# BackBoard.net
KiCad netlist of a schematic drawn in Altium Designer
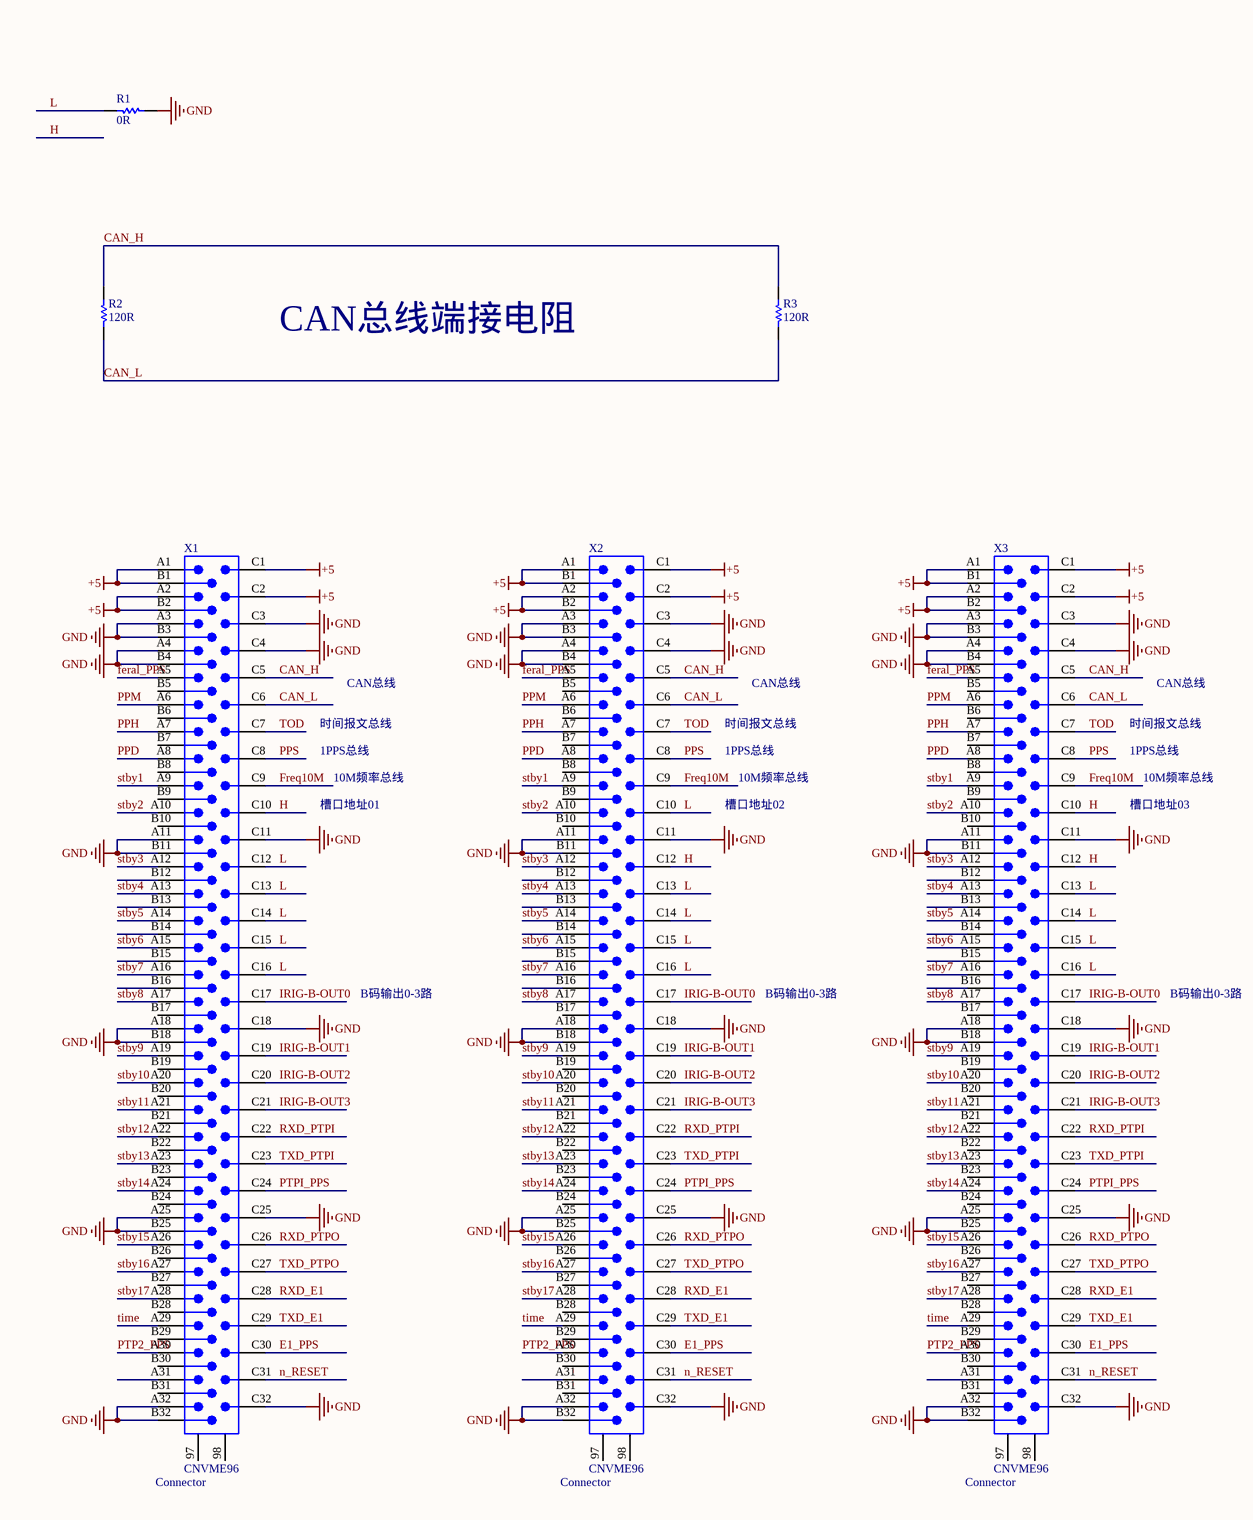
[diagram p0: BackBoard.SchDoc, top left]
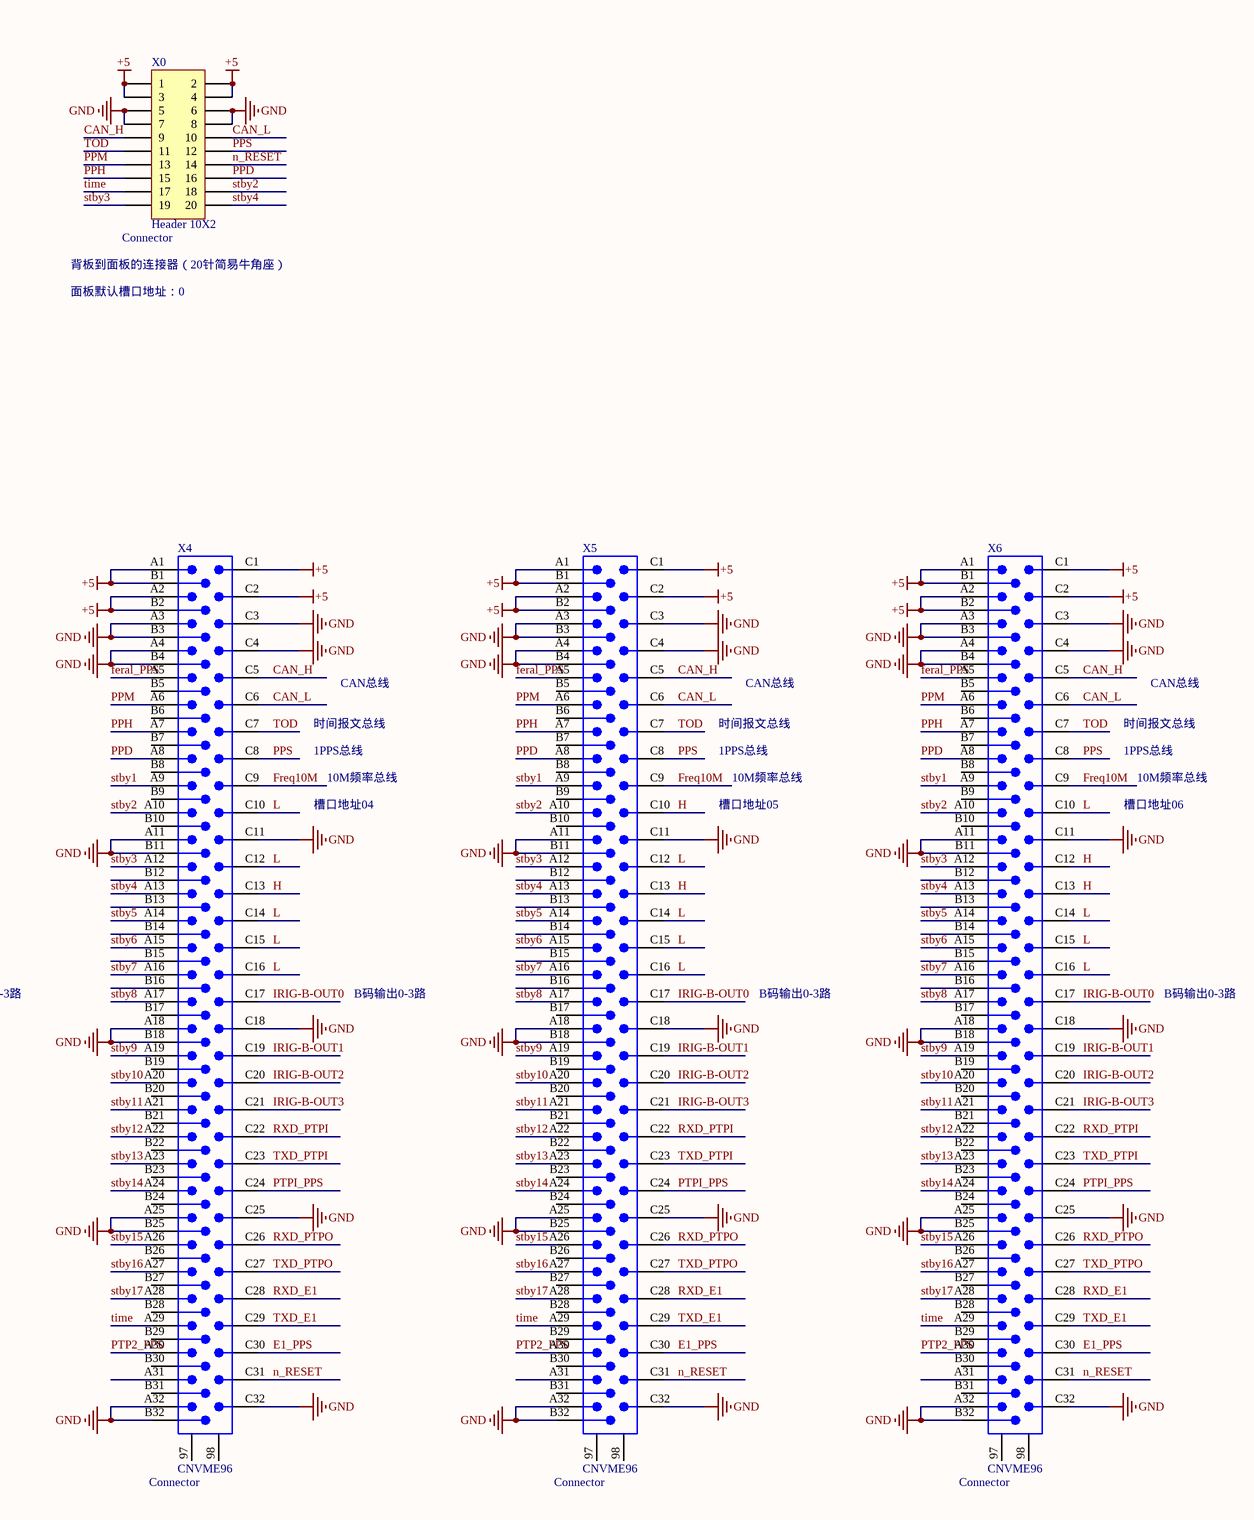
[diagram p1: BackBoard.SchDoc, top right]
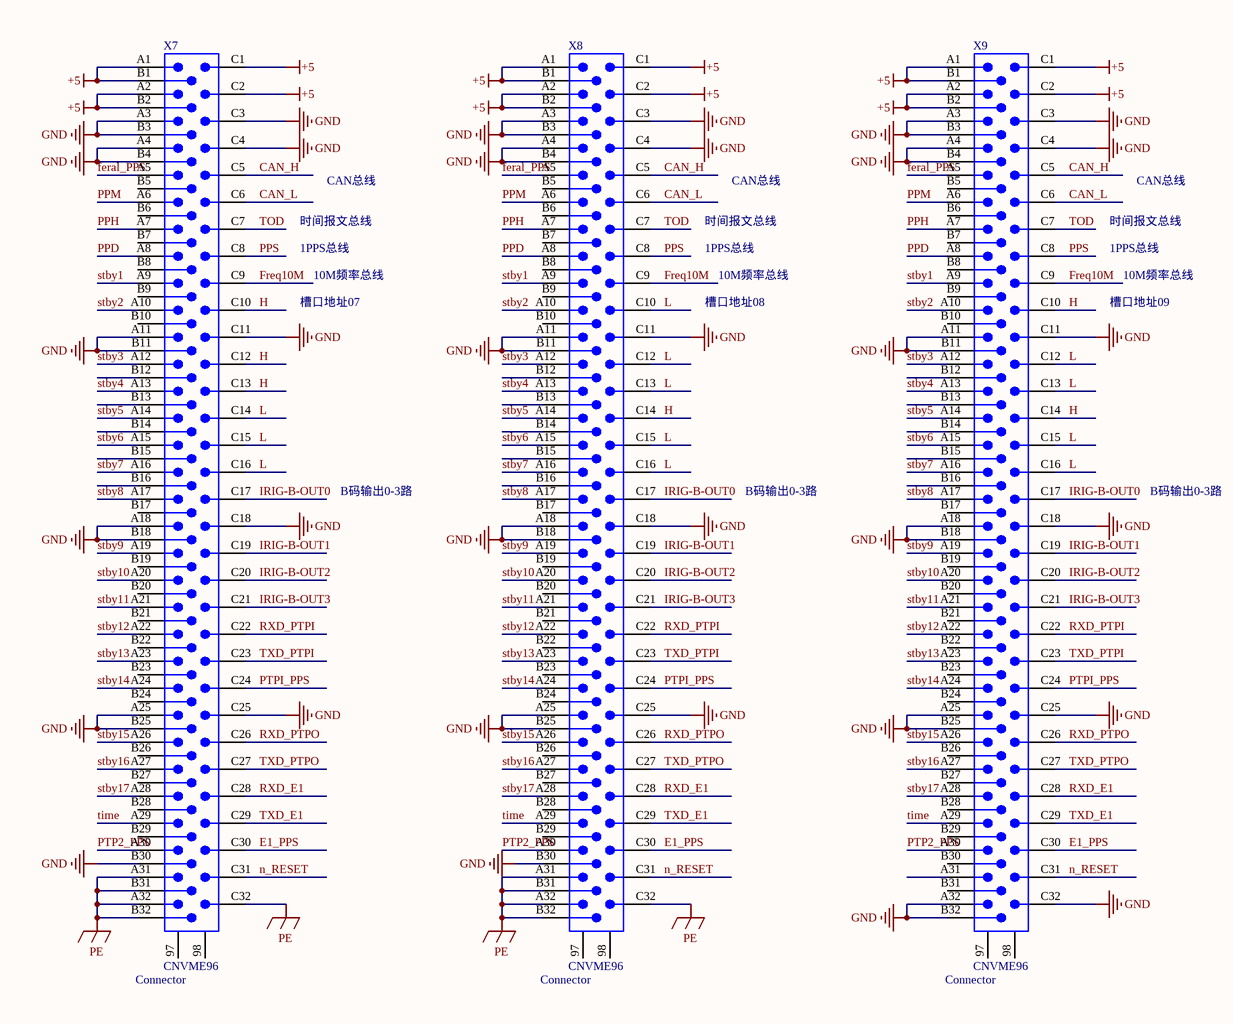
[diagram p2: BackBoard.SchDoc, bottom left]
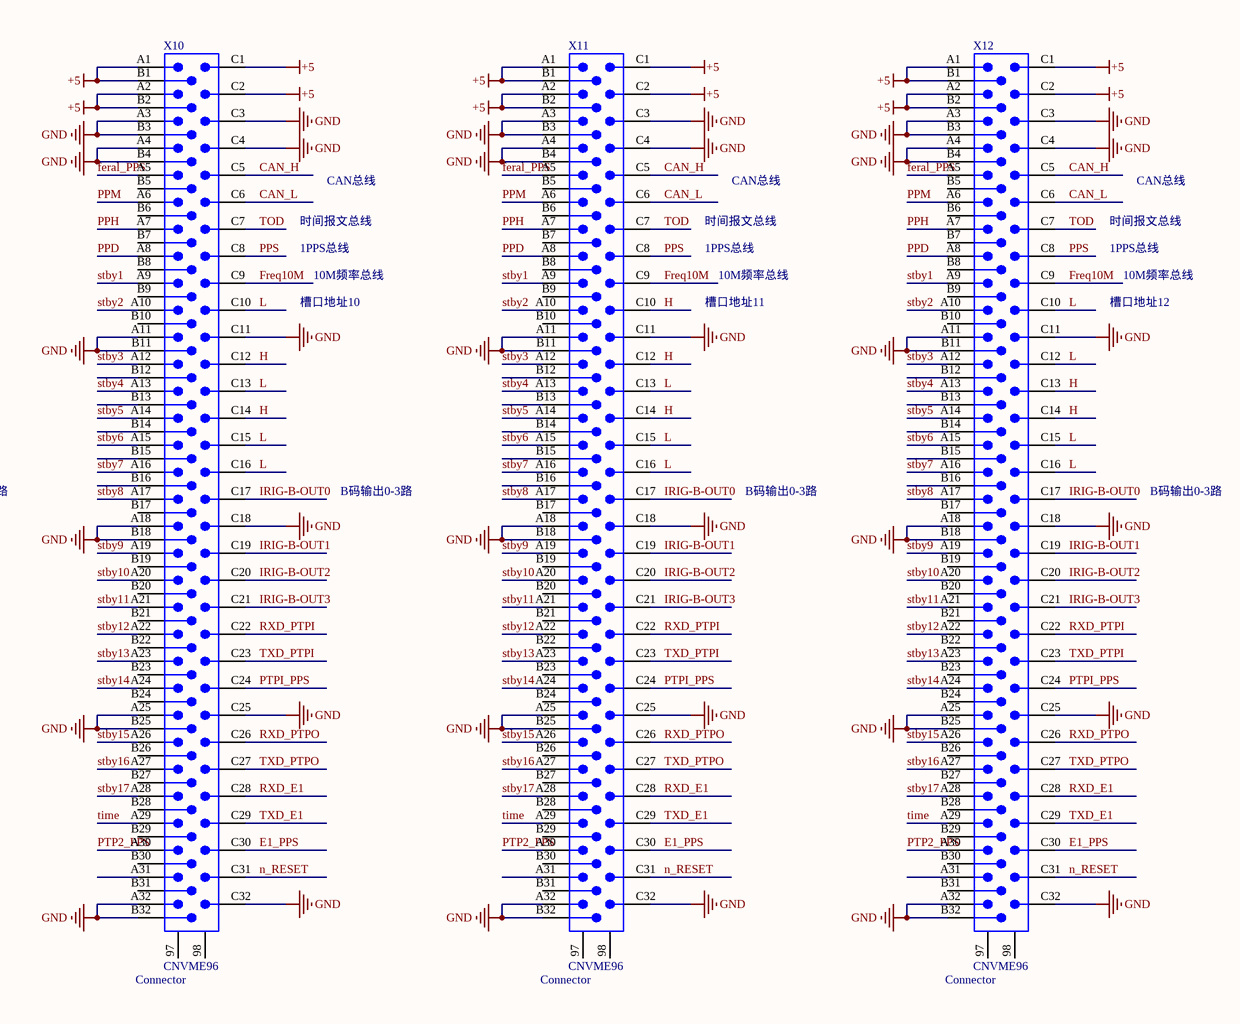
[diagram p3: BackBoard.SchDoc, bottom right]

(export (version "E")
  (design (tool "Eeschema 10.0.6"))
  (components
    (comp (ref "R1")
      (value "0R")
      (footprint "0603_XF")
      (description "Resistor")
      (fields (field (name "Comment") "Res1") (field (name "PUBLISHER") "Altium Limited"))
      (libsource (lib "Miscellaneous Devices") (part "Res1"))
    )
    (comp (ref "R2")
      (value "120R")
      (footprint "0603_XF")
      (description "Resistor")
      (fields (field (name "Comment") "Res1") (field (name "PUBLISHER") "Altium Limited"))
      (libsource (lib "Miscellaneous Devices") (part "Res1"))
    )
    (comp (ref "R3")
      (value "120R")
      (footprint "0603_XF")
      (description "Resistor")
      (fields (field (name "Comment") "Res1") (field (name "PUBLISHER") "Altium Limited"))
      (libsource (lib "Miscellaneous Devices") (part "Res1"))
    )
    (comp (ref "X0")
      (value "Header 10X2")
      (footprint "HDR2X10")
      (description "Header, 10-Pin, Dual row")
      (fields (field (name "SYSTEM") "Connector") (field (name "PUBLISHER") "Altium Limited"))
      (libsource (lib "Miscellaneous Connectors") (part "Header 10X2"))
    )
    (comp (ref "X1")
      (value "CNVME96")
      (footprint "CONNECT_96_Female")
      (description "96-Pin Connector (3x32 2.54mm grid)")
      (fields (field (name "SYSTEM") "Connector"))
      (libsource (lib "BTS4000") (part "CNVME96"))
    )
    (comp (ref "X2")
      (value "CNVME96")
      (footprint "CONNECT_96_Female")
      (description "96-Pin Connector (3x32 2.54mm grid)")
      (fields (field (name "SYSTEM") "Connector"))
      (libsource (lib "BTS4000") (part "CNVME96"))
    )
    (comp (ref "X3")
      (value "CNVME96")
      (footprint "CONNECT_96_Female")
      (description "96-Pin Connector (3x32 2.54mm grid)")
      (fields (field (name "SYSTEM") "Connector"))
      (libsource (lib "BTS4000") (part "CNVME96"))
    )
    (comp (ref "X4")
      (value "CNVME96")
      (footprint "CONNECT_96_Female")
      (description "96-Pin Connector (3x32 2.54mm grid)")
      (fields (field (name "SYSTEM") "Connector"))
      (libsource (lib "BTS4000") (part "CNVME96"))
    )
    (comp (ref "X5")
      (value "CNVME96")
      (footprint "CONNECT_96_Female")
      (description "96-Pin Connector (3x32 2.54mm grid)")
      (fields (field (name "SYSTEM") "Connector"))
      (libsource (lib "BTS4000") (part "CNVME96"))
    )
    (comp (ref "X6")
      (value "CNVME96")
      (footprint "CONNECT_96_Female")
      (description "96-Pin Connector (3x32 2.54mm grid)")
      (fields (field (name "SYSTEM") "Connector"))
      (libsource (lib "BTS4000") (part "CNVME96"))
    )
    (comp (ref "X7")
      (value "CNVME96")
      (footprint "CONNECT_96_Female")
      (description "96-Pin Connector (3x32 2.54mm grid)")
      (fields (field (name "SYSTEM") "Connector"))
      (libsource (lib "BTS4000") (part "CNVME96"))
    )
    (comp (ref "X8")
      (value "CNVME96")
      (footprint "CONNECT_96_Female")
      (description "96-Pin Connector (3x32 2.54mm grid)")
      (fields (field (name "SYSTEM") "Connector"))
      (libsource (lib "BTS4000") (part "CNVME96"))
    )
    (comp (ref "X9")
      (value "CNVME96")
      (footprint "CONNECT_96_Female")
      (description "96-Pin Connector (3x32 2.54mm grid)")
      (fields (field (name "SYSTEM") "Connector"))
      (libsource (lib "BTS4000") (part "CNVME96"))
    )
    (comp (ref "X10")
      (value "CNVME96")
      (footprint "CONNECT_96_Female")
      (description "96-Pin Connector (3x32 2.54mm grid)")
      (fields (field (name "SYSTEM") "Connector"))
      (libsource (lib "BTS4000") (part "CNVME96"))
    )
    (comp (ref "X11")
      (value "CNVME96")
      (footprint "CONNECT_96_Female")
      (description "96-Pin Connector (3x32 2.54mm grid)")
      (fields (field (name "SYSTEM") "Connector"))
      (libsource (lib "BTS4000") (part "CNVME96"))
    )
    (comp (ref "X12")
      (value "CNVME96")
      (footprint "CONNECT_96_Female")
      (description "96-Pin Connector (3x32 2.54mm grid)")
      (fields (field (name "SYSTEM") "Connector"))
      (libsource (lib "BTS4000") (part "CNVME96"))
    )
  )
  (nets
    (net (code "1") (name "+5") (class "Default")
      (node (ref "X0") (pin "1") (pinfunction "1_1") (pintype "passive"))
      (node (ref "X0") (pin "2") (pinfunction "2_2") (pintype "passive"))
      (node (ref "X0") (pin "3") (pinfunction "3_3") (pintype "passive"))
      (node (ref "X0") (pin "4") (pinfunction "4_4") (pintype "passive"))
      (node (ref "X1") (pin "A1") (pinfunction "A1_A1") (pintype "passive"))
      (node (ref "X1") (pin "A2") (pinfunction "A2_A2") (pintype "passive"))
      (node (ref "X1") (pin "B1") (pinfunction "B1_B1") (pintype "passive"))
      (node (ref "X1") (pin "B2") (pinfunction "B2_B2") (pintype "passive"))
      (node (ref "X1") (pin "C1") (pinfunction "C1_C1") (pintype "passive"))
      (node (ref "X1") (pin "C2") (pinfunction "C2_C2") (pintype "passive"))
      (node (ref "X10") (pin "A1") (pinfunction "A1_A1") (pintype "passive"))
      (node (ref "X10") (pin "A2") (pinfunction "A2_A2") (pintype "passive"))
      (node (ref "X10") (pin "B1") (pinfunction "B1_B1") (pintype "passive"))
      (node (ref "X10") (pin "B2") (pinfunction "B2_B2") (pintype "passive"))
      (node (ref "X10") (pin "C1") (pinfunction "C1_C1") (pintype "passive"))
      (node (ref "X10") (pin "C2") (pinfunction "C2_C2") (pintype "passive"))
      (node (ref "X11") (pin "A1") (pinfunction "A1_A1") (pintype "passive"))
      (node (ref "X11") (pin "A2") (pinfunction "A2_A2") (pintype "passive"))
      (node (ref "X11") (pin "B1") (pinfunction "B1_B1") (pintype "passive"))
      (node (ref "X11") (pin "B2") (pinfunction "B2_B2") (pintype "passive"))
      (node (ref "X11") (pin "C1") (pinfunction "C1_C1") (pintype "passive"))
      (node (ref "X11") (pin "C2") (pinfunction "C2_C2") (pintype "passive"))
      (node (ref "X12") (pin "A1") (pinfunction "A1_A1") (pintype "passive"))
      (node (ref "X12") (pin "A2") (pinfunction "A2_A2") (pintype "passive"))
      (node (ref "X12") (pin "B1") (pinfunction "B1_B1") (pintype "passive"))
      (node (ref "X12") (pin "B2") (pinfunction "B2_B2") (pintype "passive"))
      (node (ref "X12") (pin "C1") (pinfunction "C1_C1") (pintype "passive"))
      (node (ref "X12") (pin "C2") (pinfunction "C2_C2") (pintype "passive"))
      (node (ref "X2") (pin "A1") (pinfunction "A1_A1") (pintype "passive"))
      (node (ref "X2") (pin "A2") (pinfunction "A2_A2") (pintype "passive"))
      (node (ref "X2") (pin "B1") (pinfunction "B1_B1") (pintype "passive"))
      (node (ref "X2") (pin "B2") (pinfunction "B2_B2") (pintype "passive"))
      (node (ref "X2") (pin "C1") (pinfunction "C1_C1") (pintype "passive"))
      (node (ref "X2") (pin "C2") (pinfunction "C2_C2") (pintype "passive"))
      (node (ref "X3") (pin "A1") (pinfunction "A1_A1") (pintype "passive"))
      (node (ref "X3") (pin "A2") (pinfunction "A2_A2") (pintype "passive"))
      (node (ref "X3") (pin "B1") (pinfunction "B1_B1") (pintype "passive"))
      (node (ref "X3") (pin "B2") (pinfunction "B2_B2") (pintype "passive"))
      (node (ref "X3") (pin "C1") (pinfunction "C1_C1") (pintype "passive"))
      (node (ref "X3") (pin "C2") (pinfunction "C2_C2") (pintype "passive"))
      (node (ref "X4") (pin "A1") (pinfunction "A1_A1") (pintype "passive"))
      (node (ref "X4") (pin "A2") (pinfunction "A2_A2") (pintype "passive"))
      (node (ref "X4") (pin "B1") (pinfunction "B1_B1") (pintype "passive"))
      (node (ref "X4") (pin "B2") (pinfunction "B2_B2") (pintype "passive"))
      (node (ref "X4") (pin "C1") (pinfunction "C1_C1") (pintype "passive"))
      (node (ref "X4") (pin "C2") (pinfunction "C2_C2") (pintype "passive"))
      (node (ref "X5") (pin "A1") (pinfunction "A1_A1") (pintype "passive"))
      (node (ref "X5") (pin "A2") (pinfunction "A2_A2") (pintype "passive"))
      (node (ref "X5") (pin "B1") (pinfunction "B1_B1") (pintype "passive"))
      (node (ref "X5") (pin "B2") (pinfunction "B2_B2") (pintype "passive"))
      (node (ref "X5") (pin "C1") (pinfunction "C1_C1") (pintype "passive"))
      (node (ref "X5") (pin "C2") (pinfunction "C2_C2") (pintype "passive"))
      (node (ref "X6") (pin "A1") (pinfunction "A1_A1") (pintype "passive"))
      (node (ref "X6") (pin "A2") (pinfunction "A2_A2") (pintype "passive"))
      (node (ref "X6") (pin "B1") (pinfunction "B1_B1") (pintype "passive"))
      (node (ref "X6") (pin "B2") (pinfunction "B2_B2") (pintype "passive"))
      (node (ref "X6") (pin "C1") (pinfunction "C1_C1") (pintype "passive"))
      (node (ref "X6") (pin "C2") (pinfunction "C2_C2") (pintype "passive"))
      (node (ref "X7") (pin "A1") (pinfunction "A1_A1") (pintype "passive"))
      (node (ref "X7") (pin "A2") (pinfunction "A2_A2") (pintype "passive"))
      (node (ref "X7") (pin "B1") (pinfunction "B1_B1") (pintype "passive"))
      (node (ref "X7") (pin "B2") (pinfunction "B2_B2") (pintype "passive"))
      (node (ref "X7") (pin "C1") (pinfunction "C1_C1") (pintype "passive"))
      (node (ref "X7") (pin "C2") (pinfunction "C2_C2") (pintype "passive"))
      (node (ref "X8") (pin "A1") (pinfunction "A1_A1") (pintype "passive"))
      (node (ref "X8") (pin "A2") (pinfunction "A2_A2") (pintype "passive"))
      (node (ref "X8") (pin "B1") (pinfunction "B1_B1") (pintype "passive"))
      (node (ref "X8") (pin "B2") (pinfunction "B2_B2") (pintype "passive"))
      (node (ref "X8") (pin "C1") (pinfunction "C1_C1") (pintype "passive"))
      (node (ref "X8") (pin "C2") (pinfunction "C2_C2") (pintype "passive"))
      (node (ref "X9") (pin "A1") (pinfunction "A1_A1") (pintype "passive"))
      (node (ref "X9") (pin "A2") (pinfunction "A2_A2") (pintype "passive"))
      (node (ref "X9") (pin "B1") (pinfunction "B1_B1") (pintype "passive"))
      (node (ref "X9") (pin "B2") (pinfunction "B2_B2") (pintype "passive"))
      (node (ref "X9") (pin "C1") (pinfunction "C1_C1") (pintype "passive"))
      (node (ref "X9") (pin "C2") (pinfunction "C2_C2") (pintype "passive"))
    )
    (net (code "2") (name "/CAN_H") (class "Default")
      (node (ref "R2") (pin "1") (pinfunction "1_1") (pintype "passive"))
      (node (ref "R3") (pin "2") (pinfunction "2_2") (pintype "passive"))
      (node (ref "X0") (pin "9") (pinfunction "9_9") (pintype "passive"))
      (node (ref "X1") (pin "C5") (pinfunction "C5_C5") (pintype "passive"))
      (node (ref "X10") (pin "C5") (pinfunction "C5_C5") (pintype "passive"))
      (node (ref "X11") (pin "C5") (pinfunction "C5_C5") (pintype "passive"))
      (node (ref "X12") (pin "C5") (pinfunction "C5_C5") (pintype "passive"))
      (node (ref "X2") (pin "C5") (pinfunction "C5_C5") (pintype "passive"))
      (node (ref "X3") (pin "C5") (pinfunction "C5_C5") (pintype "passive"))
      (node (ref "X4") (pin "C5") (pinfunction "C5_C5") (pintype "passive"))
      (node (ref "X5") (pin "C5") (pinfunction "C5_C5") (pintype "passive"))
      (node (ref "X6") (pin "C5") (pinfunction "C5_C5") (pintype "passive"))
      (node (ref "X7") (pin "C5") (pinfunction "C5_C5") (pintype "passive"))
      (node (ref "X8") (pin "C5") (pinfunction "C5_C5") (pintype "passive"))
      (node (ref "X9") (pin "C5") (pinfunction "C5_C5") (pintype "passive"))
    )
    (net (code "3") (name "/CAN_L") (class "Default")
      (node (ref "R2") (pin "2") (pinfunction "2_2") (pintype "passive"))
      (node (ref "R3") (pin "1") (pinfunction "1_1") (pintype "passive"))
      (node (ref "X0") (pin "10") (pinfunction "10_10") (pintype "passive"))
      (node (ref "X1") (pin "C6") (pinfunction "C6_C6") (pintype "passive"))
      (node (ref "X10") (pin "C6") (pinfunction "C6_C6") (pintype "passive"))
      (node (ref "X11") (pin "C6") (pinfunction "C6_C6") (pintype "passive"))
      (node (ref "X12") (pin "C6") (pinfunction "C6_C6") (pintype "passive"))
      (node (ref "X2") (pin "C6") (pinfunction "C6_C6") (pintype "passive"))
      (node (ref "X3") (pin "C6") (pinfunction "C6_C6") (pintype "passive"))
      (node (ref "X4") (pin "C6") (pinfunction "C6_C6") (pintype "passive"))
      (node (ref "X5") (pin "C6") (pinfunction "C6_C6") (pintype "passive"))
      (node (ref "X6") (pin "C6") (pinfunction "C6_C6") (pintype "passive"))
      (node (ref "X7") (pin "C6") (pinfunction "C6_C6") (pintype "passive"))
      (node (ref "X8") (pin "C6") (pinfunction "C6_C6") (pintype "passive"))
      (node (ref "X9") (pin "C6") (pinfunction "C6_C6") (pintype "passive"))
    )
    (net (code "4") (name "/E1_PPS") (class "Default")
      (node (ref "X1") (pin "C30") (pinfunction "C30_C30") (pintype "passive"))
      (node (ref "X10") (pin "C30") (pinfunction "C30_C30") (pintype "passive"))
      (node (ref "X11") (pin "C30") (pinfunction "C30_C30") (pintype "passive"))
      (node (ref "X12") (pin "C30") (pinfunction "C30_C30") (pintype "passive"))
      (node (ref "X2") (pin "C30") (pinfunction "C30_C30") (pintype "passive"))
      (node (ref "X3") (pin "C30") (pinfunction "C30_C30") (pintype "passive"))
      (node (ref "X4") (pin "C30") (pinfunction "C30_C30") (pintype "passive"))
      (node (ref "X5") (pin "C30") (pinfunction "C30_C30") (pintype "passive"))
      (node (ref "X6") (pin "C30") (pinfunction "C30_C30") (pintype "passive"))
      (node (ref "X7") (pin "C30") (pinfunction "C30_C30") (pintype "passive"))
      (node (ref "X8") (pin "C30") (pinfunction "C30_C30") (pintype "passive"))
      (node (ref "X9") (pin "C30") (pinfunction "C30_C30") (pintype "passive"))
    )
    (net (code "5") (name "/Freq10M") (class "Default")
      (node (ref "X1") (pin "C9") (pinfunction "C9_C9") (pintype "passive"))
      (node (ref "X10") (pin "C9") (pinfunction "C9_C9") (pintype "passive"))
      (node (ref "X11") (pin "C9") (pinfunction "C9_C9") (pintype "passive"))
      (node (ref "X12") (pin "C9") (pinfunction "C9_C9") (pintype "passive"))
      (node (ref "X2") (pin "C9") (pinfunction "C9_C9") (pintype "passive"))
      (node (ref "X3") (pin "C9") (pinfunction "C9_C9") (pintype "passive"))
      (node (ref "X4") (pin "C9") (pinfunction "C9_C9") (pintype "passive"))
      (node (ref "X5") (pin "C9") (pinfunction "C9_C9") (pintype "passive"))
      (node (ref "X6") (pin "C9") (pinfunction "C9_C9") (pintype "passive"))
      (node (ref "X7") (pin "C9") (pinfunction "C9_C9") (pintype "passive"))
      (node (ref "X8") (pin "C9") (pinfunction "C9_C9") (pintype "passive"))
      (node (ref "X9") (pin "C9") (pinfunction "C9_C9") (pintype "passive"))
    )
    (net (code "6") (name "/H") (class "Default")
      (node (ref "X1") (pin "C10") (pinfunction "C10_C10") (pintype "passive"))
      (node (ref "X10") (pin "C12") (pinfunction "C12_C12") (pintype "passive"))
      (node (ref "X10") (pin "C14") (pinfunction "C14_C14") (pintype "passive"))
      (node (ref "X11") (pin "C10") (pinfunction "C10_C10") (pintype "passive"))
      (node (ref "X11") (pin "C12") (pinfunction "C12_C12") (pintype "passive"))
      (node (ref "X11") (pin "C14") (pinfunction "C14_C14") (pintype "passive"))
      (node (ref "X12") (pin "C13") (pinfunction "C13_C13") (pintype "passive"))
      (node (ref "X12") (pin "C14") (pinfunction "C14_C14") (pintype "passive"))
      (node (ref "X2") (pin "C12") (pinfunction "C12_C12") (pintype "passive"))
      (node (ref "X3") (pin "C10") (pinfunction "C10_C10") (pintype "passive"))
      (node (ref "X3") (pin "C12") (pinfunction "C12_C12") (pintype "passive"))
      (node (ref "X4") (pin "C13") (pinfunction "C13_C13") (pintype "passive"))
      (node (ref "X5") (pin "C10") (pinfunction "C10_C10") (pintype "passive"))
      (node (ref "X5") (pin "C13") (pinfunction "C13_C13") (pintype "passive"))
      (node (ref "X6") (pin "C12") (pinfunction "C12_C12") (pintype "passive"))
      (node (ref "X6") (pin "C13") (pinfunction "C13_C13") (pintype "passive"))
      (node (ref "X7") (pin "C10") (pinfunction "C10_C10") (pintype "passive"))
      (node (ref "X7") (pin "C12") (pinfunction "C12_C12") (pintype "passive"))
      (node (ref "X7") (pin "C13") (pinfunction "C13_C13") (pintype "passive"))
      (node (ref "X8") (pin "C14") (pinfunction "C14_C14") (pintype "passive"))
      (node (ref "X9") (pin "C10") (pinfunction "C10_C10") (pintype "passive"))
      (node (ref "X9") (pin "C14") (pinfunction "C14_C14") (pintype "passive"))
    )
    (net (code "7") (name "/IRIG-B-OUT0") (class "Default")
      (node (ref "X1") (pin "C17") (pinfunction "C17_C17") (pintype "passive"))
      (node (ref "X10") (pin "C17") (pinfunction "C17_C17") (pintype "passive"))
      (node (ref "X11") (pin "C17") (pinfunction "C17_C17") (pintype "passive"))
      (node (ref "X12") (pin "C17") (pinfunction "C17_C17") (pintype "passive"))
      (node (ref "X2") (pin "C17") (pinfunction "C17_C17") (pintype "passive"))
      (node (ref "X3") (pin "C17") (pinfunction "C17_C17") (pintype "passive"))
      (node (ref "X4") (pin "C17") (pinfunction "C17_C17") (pintype "passive"))
      (node (ref "X5") (pin "C17") (pinfunction "C17_C17") (pintype "passive"))
      (node (ref "X6") (pin "C17") (pinfunction "C17_C17") (pintype "passive"))
      (node (ref "X7") (pin "C17") (pinfunction "C17_C17") (pintype "passive"))
      (node (ref "X8") (pin "C17") (pinfunction "C17_C17") (pintype "passive"))
      (node (ref "X9") (pin "C17") (pinfunction "C17_C17") (pintype "passive"))
    )
    (net (code "8") (name "/IRIG-B-OUT1") (class "Default")
      (node (ref "X1") (pin "C19") (pinfunction "C19_C19") (pintype "passive"))
      (node (ref "X10") (pin "C19") (pinfunction "C19_C19") (pintype "passive"))
      (node (ref "X11") (pin "C19") (pinfunction "C19_C19") (pintype "passive"))
      (node (ref "X12") (pin "C19") (pinfunction "C19_C19") (pintype "passive"))
      (node (ref "X2") (pin "C19") (pinfunction "C19_C19") (pintype "passive"))
      (node (ref "X3") (pin "C19") (pinfunction "C19_C19") (pintype "passive"))
      (node (ref "X4") (pin "C19") (pinfunction "C19_C19") (pintype "passive"))
      (node (ref "X5") (pin "C19") (pinfunction "C19_C19") (pintype "passive"))
      (node (ref "X6") (pin "C19") (pinfunction "C19_C19") (pintype "passive"))
      (node (ref "X7") (pin "C19") (pinfunction "C19_C19") (pintype "passive"))
      (node (ref "X8") (pin "C19") (pinfunction "C19_C19") (pintype "passive"))
      (node (ref "X9") (pin "C19") (pinfunction "C19_C19") (pintype "passive"))
    )
    (net (code "9") (name "/IRIG-B-OUT2") (class "Default")
      (node (ref "X1") (pin "C20") (pinfunction "C20_C20") (pintype "passive"))
      (node (ref "X10") (pin "C20") (pinfunction "C20_C20") (pintype "passive"))
      (node (ref "X11") (pin "C20") (pinfunction "C20_C20") (pintype "passive"))
      (node (ref "X12") (pin "C20") (pinfunction "C20_C20") (pintype "passive"))
      (node (ref "X2") (pin "C20") (pinfunction "C20_C20") (pintype "passive"))
      (node (ref "X3") (pin "C20") (pinfunction "C20_C20") (pintype "passive"))
      (node (ref "X4") (pin "C20") (pinfunction "C20_C20") (pintype "passive"))
      (node (ref "X5") (pin "C20") (pinfunction "C20_C20") (pintype "passive"))
      (node (ref "X6") (pin "C20") (pinfunction "C20_C20") (pintype "passive"))
      (node (ref "X7") (pin "C20") (pinfunction "C20_C20") (pintype "passive"))
      (node (ref "X8") (pin "C20") (pinfunction "C20_C20") (pintype "passive"))
      (node (ref "X9") (pin "C20") (pinfunction "C20_C20") (pintype "passive"))
    )
    (net (code "10") (name "/IRIG-B-OUT3") (class "Default")
      (node (ref "X1") (pin "C21") (pinfunction "C21_C21") (pintype "passive"))
      (node (ref "X10") (pin "C21") (pinfunction "C21_C21") (pintype "passive"))
      (node (ref "X11") (pin "C21") (pinfunction "C21_C21") (pintype "passive"))
      (node (ref "X12") (pin "C21") (pinfunction "C21_C21") (pintype "passive"))
      (node (ref "X2") (pin "C21") (pinfunction "C21_C21") (pintype "passive"))
      (node (ref "X3") (pin "C21") (pinfunction "C21_C21") (pintype "passive"))
      (node (ref "X4") (pin "C21") (pinfunction "C21_C21") (pintype "passive"))
      (node (ref "X5") (pin "C21") (pinfunction "C21_C21") (pintype "passive"))
      (node (ref "X6") (pin "C21") (pinfunction "C21_C21") (pintype "passive"))
      (node (ref "X7") (pin "C21") (pinfunction "C21_C21") (pintype "passive"))
      (node (ref "X8") (pin "C21") (pinfunction "C21_C21") (pintype "passive"))
      (node (ref "X9") (pin "C21") (pinfunction "C21_C21") (pintype "passive"))
    )
    (net (code "11") (name "/L") (class "Default")
      (node (ref "R1") (pin "1") (pinfunction "1_1") (pintype "passive"))
      (node (ref "X1") (pin "C12") (pinfunction "C12_C12") (pintype "passive"))
      (node (ref "X1") (pin "C13") (pinfunction "C13_C13") (pintype "passive"))
      (node (ref "X1") (pin "C14") (pinfunction "C14_C14") (pintype "passive"))
      (node (ref "X1") (pin "C15") (pinfunction "C15_C15") (pintype "passive"))
      (node (ref "X1") (pin "C16") (pinfunction "C16_C16") (pintype "passive"))
      (node (ref "X10") (pin "C10") (pinfunction "C10_C10") (pintype "passive"))
      (node (ref "X10") (pin "C13") (pinfunction "C13_C13") (pintype "passive"))
      (node (ref "X10") (pin "C15") (pinfunction "C15_C15") (pintype "passive"))
      (node (ref "X10") (pin "C16") (pinfunction "C16_C16") (pintype "passive"))
      (node (ref "X11") (pin "C13") (pinfunction "C13_C13") (pintype "passive"))
      (node (ref "X11") (pin "C15") (pinfunction "C15_C15") (pintype "passive"))
      (node (ref "X11") (pin "C16") (pinfunction "C16_C16") (pintype "passive"))
      (node (ref "X12") (pin "C10") (pinfunction "C10_C10") (pintype "passive"))
      (node (ref "X12") (pin "C12") (pinfunction "C12_C12") (pintype "passive"))
      (node (ref "X12") (pin "C15") (pinfunction "C15_C15") (pintype "passive"))
      (node (ref "X12") (pin "C16") (pinfunction "C16_C16") (pintype "passive"))
      (node (ref "X2") (pin "C10") (pinfunction "C10_C10") (pintype "passive"))
      (node (ref "X2") (pin "C13") (pinfunction "C13_C13") (pintype "passive"))
      (node (ref "X2") (pin "C14") (pinfunction "C14_C14") (pintype "passive"))
      (node (ref "X2") (pin "C15") (pinfunction "C15_C15") (pintype "passive"))
      (node (ref "X2") (pin "C16") (pinfunction "C16_C16") (pintype "passive"))
      (node (ref "X3") (pin "C13") (pinfunction "C13_C13") (pintype "passive"))
      (node (ref "X3") (pin "C14") (pinfunction "C14_C14") (pintype "passive"))
      (node (ref "X3") (pin "C15") (pinfunction "C15_C15") (pintype "passive"))
      (node (ref "X3") (pin "C16") (pinfunction "C16_C16") (pintype "passive"))
      (node (ref "X4") (pin "C10") (pinfunction "C10_C10") (pintype "passive"))
      (node (ref "X4") (pin "C12") (pinfunction "C12_C12") (pintype "passive"))
      (node (ref "X4") (pin "C14") (pinfunction "C14_C14") (pintype "passive"))
      (node (ref "X4") (pin "C15") (pinfunction "C15_C15") (pintype "passive"))
      (node (ref "X4") (pin "C16") (pinfunction "C16_C16") (pintype "passive"))
      (node (ref "X5") (pin "C12") (pinfunction "C12_C12") (pintype "passive"))
      (node (ref "X5") (pin "C14") (pinfunction "C14_C14") (pintype "passive"))
      (node (ref "X5") (pin "C15") (pinfunction "C15_C15") (pintype "passive"))
      (node (ref "X5") (pin "C16") (pinfunction "C16_C16") (pintype "passive"))
      (node (ref "X6") (pin "C10") (pinfunction "C10_C10") (pintype "passive"))
      (node (ref "X6") (pin "C14") (pinfunction "C14_C14") (pintype "passive"))
      (node (ref "X6") (pin "C15") (pinfunction "C15_C15") (pintype "passive"))
      (node (ref "X6") (pin "C16") (pinfunction "C16_C16") (pintype "passive"))
      (node (ref "X7") (pin "C14") (pinfunction "C14_C14") (pintype "passive"))
      (node (ref "X7") (pin "C15") (pinfunction "C15_C15") (pintype "passive"))
      (node (ref "X7") (pin "C16") (pinfunction "C16_C16") (pintype "passive"))
      (node (ref "X8") (pin "C10") (pinfunction "C10_C10") (pintype "passive"))
      (node (ref "X8") (pin "C12") (pinfunction "C12_C12") (pintype "passive"))
      (node (ref "X8") (pin "C13") (pinfunction "C13_C13") (pintype "passive"))
      (node (ref "X8") (pin "C15") (pinfunction "C15_C15") (pintype "passive"))
      (node (ref "X8") (pin "C16") (pinfunction "C16_C16") (pintype "passive"))
      (node (ref "X9") (pin "C12") (pinfunction "C12_C12") (pintype "passive"))
      (node (ref "X9") (pin "C13") (pinfunction "C13_C13") (pintype "passive"))
      (node (ref "X9") (pin "C15") (pinfunction "C15_C15") (pintype "passive"))
      (node (ref "X9") (pin "C16") (pinfunction "C16_C16") (pintype "passive"))
    )
    (net (code "12") (name "/PPD") (class "Default")
      (node (ref "X0") (pin "16") (pinfunction "16_16") (pintype "passive"))
      (node (ref "X1") (pin "A8") (pinfunction "A8_A8") (pintype "passive"))
      (node (ref "X10") (pin "A8") (pinfunction "A8_A8") (pintype "passive"))
      (node (ref "X11") (pin "A8") (pinfunction "A8_A8") (pintype "passive"))
      (node (ref "X12") (pin "A8") (pinfunction "A8_A8") (pintype "passive"))
      (node (ref "X2") (pin "A8") (pinfunction "A8_A8") (pintype "passive"))
      (node (ref "X3") (pin "A8") (pinfunction "A8_A8") (pintype "passive"))
      (node (ref "X4") (pin "A8") (pinfunction "A8_A8") (pintype "passive"))
      (node (ref "X5") (pin "A8") (pinfunction "A8_A8") (pintype "passive"))
      (node (ref "X6") (pin "A8") (pinfunction "A8_A8") (pintype "passive"))
      (node (ref "X7") (pin "A8") (pinfunction "A8_A8") (pintype "passive"))
      (node (ref "X8") (pin "A8") (pinfunction "A8_A8") (pintype "passive"))
      (node (ref "X9") (pin "A8") (pinfunction "A8_A8") (pintype "passive"))
    )
    (net (code "13") (name "/PPH") (class "Default")
      (node (ref "X0") (pin "15") (pinfunction "15_15") (pintype "passive"))
      (node (ref "X1") (pin "A7") (pinfunction "A7_A7") (pintype "passive"))
      (node (ref "X10") (pin "A7") (pinfunction "A7_A7") (pintype "passive"))
      (node (ref "X11") (pin "A7") (pinfunction "A7_A7") (pintype "passive"))
      (node (ref "X12") (pin "A7") (pinfunction "A7_A7") (pintype "passive"))
      (node (ref "X2") (pin "A7") (pinfunction "A7_A7") (pintype "passive"))
      (node (ref "X3") (pin "A7") (pinfunction "A7_A7") (pintype "passive"))
      (node (ref "X4") (pin "A7") (pinfunction "A7_A7") (pintype "passive"))
      (node (ref "X5") (pin "A7") (pinfunction "A7_A7") (pintype "passive"))
      (node (ref "X6") (pin "A7") (pinfunction "A7_A7") (pintype "passive"))
      (node (ref "X7") (pin "A7") (pinfunction "A7_A7") (pintype "passive"))
      (node (ref "X8") (pin "A7") (pinfunction "A7_A7") (pintype "passive"))
      (node (ref "X9") (pin "A7") (pinfunction "A7_A7") (pintype "passive"))
    )
    (net (code "14") (name "/PPM") (class "Default")
      (node (ref "X0") (pin "13") (pinfunction "13_13") (pintype "passive"))
      (node (ref "X1") (pin "A6") (pinfunction "A6_A6") (pintype "passive"))
      (node (ref "X10") (pin "A6") (pinfunction "A6_A6") (pintype "passive"))
      (node (ref "X11") (pin "A6") (pinfunction "A6_A6") (pintype "passive"))
      (node (ref "X12") (pin "A6") (pinfunction "A6_A6") (pintype "passive"))
      (node (ref "X2") (pin "A6") (pinfunction "A6_A6") (pintype "passive"))
      (node (ref "X3") (pin "A6") (pinfunction "A6_A6") (pintype "passive"))
      (node (ref "X4") (pin "A6") (pinfunction "A6_A6") (pintype "passive"))
      (node (ref "X5") (pin "A6") (pinfunction "A6_A6") (pintype "passive"))
      (node (ref "X6") (pin "A6") (pinfunction "A6_A6") (pintype "passive"))
      (node (ref "X7") (pin "A6") (pinfunction "A6_A6") (pintype "passive"))
      (node (ref "X8") (pin "A6") (pinfunction "A6_A6") (pintype "passive"))
      (node (ref "X9") (pin "A6") (pinfunction "A6_A6") (pintype "passive"))
    )
    (net (code "15") (name "/PPS") (class "Default")
      (node (ref "X0") (pin "12") (pinfunction "12_12") (pintype "passive"))
      (node (ref "X1") (pin "C8") (pinfunction "C8_C8") (pintype "passive"))
      (node (ref "X10") (pin "C8") (pinfunction "C8_C8") (pintype "passive"))
      (node (ref "X11") (pin "C8") (pinfunction "C8_C8") (pintype "passive"))
      (node (ref "X12") (pin "C8") (pinfunction "C8_C8") (pintype "passive"))
      (node (ref "X2") (pin "C8") (pinfunction "C8_C8") (pintype "passive"))
      (node (ref "X3") (pin "C8") (pinfunction "C8_C8") (pintype "passive"))
      (node (ref "X4") (pin "C8") (pinfunction "C8_C8") (pintype "passive"))
      (node (ref "X5") (pin "C8") (pinfunction "C8_C8") (pintype "passive"))
      (node (ref "X6") (pin "C8") (pinfunction "C8_C8") (pintype "passive"))
      (node (ref "X7") (pin "C8") (pinfunction "C8_C8") (pintype "passive"))
      (node (ref "X8") (pin "C8") (pinfunction "C8_C8") (pintype "passive"))
      (node (ref "X9") (pin "C8") (pinfunction "C8_C8") (pintype "passive"))
    )
    (net (code "16") (name "/PTP2_PPS") (class "Default")
      (node (ref "X1") (pin "A30") (pinfunction "A30_A30") (pintype "passive"))
      (node (ref "X10") (pin "A30") (pinfunction "A30_A30") (pintype "passive"))
      (node (ref "X11") (pin "A30") (pinfunction "A30_A30") (pintype "passive"))
      (node (ref "X12") (pin "A30") (pinfunction "A30_A30") (pintype "passive"))
      (node (ref "X2") (pin "A30") (pinfunction "A30_A30") (pintype "passive"))
      (node (ref "X3") (pin "A30") (pinfunction "A30_A30") (pintype "passive"))
      (node (ref "X4") (pin "A30") (pinfunction "A30_A30") (pintype "passive"))
      (node (ref "X5") (pin "A30") (pinfunction "A30_A30") (pintype "passive"))
      (node (ref "X6") (pin "A30") (pinfunction "A30_A30") (pintype "passive"))
      (node (ref "X7") (pin "A30") (pinfunction "A30_A30") (pintype "passive"))
      (node (ref "X8") (pin "A30") (pinfunction "A30_A30") (pintype "passive"))
      (node (ref "X9") (pin "A30") (pinfunction "A30_A30") (pintype "passive"))
    )
    (net (code "17") (name "/PTPI_PPS") (class "Default")
      (node (ref "X1") (pin "C24") (pinfunction "C24_C24") (pintype "passive"))
      (node (ref "X10") (pin "C24") (pinfunction "C24_C24") (pintype "passive"))
      (node (ref "X11") (pin "C24") (pinfunction "C24_C24") (pintype "passive"))
      (node (ref "X12") (pin "C24") (pinfunction "C24_C24") (pintype "passive"))
      (node (ref "X2") (pin "C24") (pinfunction "C24_C24") (pintype "passive"))
      (node (ref "X3") (pin "C24") (pinfunction "C24_C24") (pintype "passive"))
      (node (ref "X4") (pin "C24") (pinfunction "C24_C24") (pintype "passive"))
      (node (ref "X5") (pin "C24") (pinfunction "C24_C24") (pintype "passive"))
      (node (ref "X6") (pin "C24") (pinfunction "C24_C24") (pintype "passive"))
      (node (ref "X7") (pin "C24") (pinfunction "C24_C24") (pintype "passive"))
      (node (ref "X8") (pin "C24") (pinfunction "C24_C24") (pintype "passive"))
      (node (ref "X9") (pin "C24") (pinfunction "C24_C24") (pintype "passive"))
    )
    (net (code "18") (name "/RXD_E1") (class "Default")
      (node (ref "X1") (pin "C28") (pinfunction "C28_C28") (pintype "passive"))
      (node (ref "X10") (pin "C28") (pinfunction "C28_C28") (pintype "passive"))
      (node (ref "X11") (pin "C28") (pinfunction "C28_C28") (pintype "passive"))
      (node (ref "X12") (pin "C28") (pinfunction "C28_C28") (pintype "passive"))
      (node (ref "X2") (pin "C28") (pinfunction "C28_C28") (pintype "passive"))
      (node (ref "X3") (pin "C28") (pinfunction "C28_C28") (pintype "passive"))
      (node (ref "X4") (pin "C28") (pinfunction "C28_C28") (pintype "passive"))
      (node (ref "X5") (pin "C28") (pinfunction "C28_C28") (pintype "passive"))
      (node (ref "X6") (pin "C28") (pinfunction "C28_C28") (pintype "passive"))
      (node (ref "X7") (pin "C28") (pinfunction "C28_C28") (pintype "passive"))
      (node (ref "X8") (pin "C28") (pinfunction "C28_C28") (pintype "passive"))
      (node (ref "X9") (pin "C28") (pinfunction "C28_C28") (pintype "passive"))
    )
    (net (code "19") (name "/RXD_PTPI") (class "Default")
      (node (ref "X1") (pin "C22") (pinfunction "C22_C22") (pintype "passive"))
      (node (ref "X10") (pin "C22") (pinfunction "C22_C22") (pintype "passive"))
      (node (ref "X11") (pin "C22") (pinfunction "C22_C22") (pintype "passive"))
      (node (ref "X12") (pin "C22") (pinfunction "C22_C22") (pintype "passive"))
      (node (ref "X2") (pin "C22") (pinfunction "C22_C22") (pintype "passive"))
      (node (ref "X3") (pin "C22") (pinfunction "C22_C22") (pintype "passive"))
      (node (ref "X4") (pin "C22") (pinfunction "C22_C22") (pintype "passive"))
      (node (ref "X5") (pin "C22") (pinfunction "C22_C22") (pintype "passive"))
      (node (ref "X6") (pin "C22") (pinfunction "C22_C22") (pintype "passive"))
      (node (ref "X7") (pin "C22") (pinfunction "C22_C22") (pintype "passive"))
      (node (ref "X8") (pin "C22") (pinfunction "C22_C22") (pintype "passive"))
      (node (ref "X9") (pin "C22") (pinfunction "C22_C22") (pintype "passive"))
    )
    (net (code "20") (name "/RXD_PTPO") (class "Default")
      (node (ref "X1") (pin "C26") (pinfunction "C26_C26") (pintype "passive"))
      (node (ref "X10") (pin "C26") (pinfunction "C26_C26") (pintype "passive"))
      (node (ref "X11") (pin "C26") (pinfunction "C26_C26") (pintype "passive"))
      (node (ref "X12") (pin "C26") (pinfunction "C26_C26") (pintype "passive"))
      (node (ref "X2") (pin "C26") (pinfunction "C26_C26") (pintype "passive"))
      (node (ref "X3") (pin "C26") (pinfunction "C26_C26") (pintype "passive"))
      (node (ref "X4") (pin "C26") (pinfunction "C26_C26") (pintype "passive"))
      (node (ref "X5") (pin "C26") (pinfunction "C26_C26") (pintype "passive"))
      (node (ref "X6") (pin "C26") (pinfunction "C26_C26") (pintype "passive"))
      (node (ref "X7") (pin "C26") (pinfunction "C26_C26") (pintype "passive"))
      (node (ref "X8") (pin "C26") (pinfunction "C26_C26") (pintype "passive"))
      (node (ref "X9") (pin "C26") (pinfunction "C26_C26") (pintype "passive"))
    )
    (net (code "21") (name "/TOD") (class "Default")
      (node (ref "X0") (pin "11") (pinfunction "11_11") (pintype "passive"))
      (node (ref "X1") (pin "C7") (pinfunction "C7_C7") (pintype "passive"))
      (node (ref "X10") (pin "C7") (pinfunction "C7_C7") (pintype "passive"))
      (node (ref "X11") (pin "C7") (pinfunction "C7_C7") (pintype "passive"))
      (node (ref "X12") (pin "C7") (pinfunction "C7_C7") (pintype "passive"))
      (node (ref "X2") (pin "C7") (pinfunction "C7_C7") (pintype "passive"))
      (node (ref "X3") (pin "C7") (pinfunction "C7_C7") (pintype "passive"))
      (node (ref "X4") (pin "C7") (pinfunction "C7_C7") (pintype "passive"))
      (node (ref "X5") (pin "C7") (pinfunction "C7_C7") (pintype "passive"))
      (node (ref "X6") (pin "C7") (pinfunction "C7_C7") (pintype "passive"))
      (node (ref "X7") (pin "C7") (pinfunction "C7_C7") (pintype "passive"))
      (node (ref "X8") (pin "C7") (pinfunction "C7_C7") (pintype "passive"))
      (node (ref "X9") (pin "C7") (pinfunction "C7_C7") (pintype "passive"))
    )
    (net (code "22") (name "/TXD_E1") (class "Default")
      (node (ref "X1") (pin "C29") (pinfunction "C29_C29") (pintype "passive"))
      (node (ref "X10") (pin "C29") (pinfunction "C29_C29") (pintype "passive"))
      (node (ref "X11") (pin "C29") (pinfunction "C29_C29") (pintype "passive"))
      (node (ref "X12") (pin "C29") (pinfunction "C29_C29") (pintype "passive"))
      (node (ref "X2") (pin "C29") (pinfunction "C29_C29") (pintype "passive"))
      (node (ref "X3") (pin "C29") (pinfunction "C29_C29") (pintype "passive"))
      (node (ref "X4") (pin "C29") (pinfunction "C29_C29") (pintype "passive"))
      (node (ref "X5") (pin "C29") (pinfunction "C29_C29") (pintype "passive"))
      (node (ref "X6") (pin "C29") (pinfunction "C29_C29") (pintype "passive"))
      (node (ref "X7") (pin "C29") (pinfunction "C29_C29") (pintype "passive"))
      (node (ref "X8") (pin "C29") (pinfunction "C29_C29") (pintype "passive"))
      (node (ref "X9") (pin "C29") (pinfunction "C29_C29") (pintype "passive"))
    )
    (net (code "23") (name "/TXD_PTPI") (class "Default")
      (node (ref "X1") (pin "C23") (pinfunction "C23_C23") (pintype "passive"))
      (node (ref "X10") (pin "C23") (pinfunction "C23_C23") (pintype "passive"))
      (node (ref "X11") (pin "C23") (pinfunction "C23_C23") (pintype "passive"))
      (node (ref "X12") (pin "C23") (pinfunction "C23_C23") (pintype "passive"))
      (node (ref "X2") (pin "C23") (pinfunction "C23_C23") (pintype "passive"))
      (node (ref "X3") (pin "C23") (pinfunction "C23_C23") (pintype "passive"))
      (node (ref "X4") (pin "C23") (pinfunction "C23_C23") (pintype "passive"))
      (node (ref "X5") (pin "C23") (pinfunction "C23_C23") (pintype "passive"))
      (node (ref "X6") (pin "C23") (pinfunction "C23_C23") (pintype "passive"))
      (node (ref "X7") (pin "C23") (pinfunction "C23_C23") (pintype "passive"))
      (node (ref "X8") (pin "C23") (pinfunction "C23_C23") (pintype "passive"))
      (node (ref "X9") (pin "C23") (pinfunction "C23_C23") (pintype "passive"))
    )
    (net (code "24") (name "/TXD_PTPO") (class "Default")
      (node (ref "X1") (pin "C27") (pinfunction "C27_C27") (pintype "passive"))
      (node (ref "X10") (pin "C27") (pinfunction "C27_C27") (pintype "passive"))
      (node (ref "X11") (pin "C27") (pinfunction "C27_C27") (pintype "passive"))
      (node (ref "X12") (pin "C27") (pinfunction "C27_C27") (pintype "passive"))
      (node (ref "X2") (pin "C27") (pinfunction "C27_C27") (pintype "passive"))
      (node (ref "X3") (pin "C27") (pinfunction "C27_C27") (pintype "passive"))
      (node (ref "X4") (pin "C27") (pinfunction "C27_C27") (pintype "passive"))
      (node (ref "X5") (pin "C27") (pinfunction "C27_C27") (pintype "passive"))
      (node (ref "X6") (pin "C27") (pinfunction "C27_C27") (pintype "passive"))
      (node (ref "X7") (pin "C27") (pinfunction "C27_C27") (pintype "passive"))
      (node (ref "X8") (pin "C27") (pinfunction "C27_C27") (pintype "passive"))
      (node (ref "X9") (pin "C27") (pinfunction "C27_C27") (pintype "passive"))
    )
    (net (code "25") (name "/feral_PPS") (class "Default")
      (node (ref "X1") (pin "A5") (pinfunction "A5_A5") (pintype "passive"))
      (node (ref "X10") (pin "A5") (pinfunction "A5_A5") (pintype "passive"))
      (node (ref "X11") (pin "A5") (pinfunction "A5_A5") (pintype "passive"))
      (node (ref "X12") (pin "A5") (pinfunction "A5_A5") (pintype "passive"))
      (node (ref "X2") (pin "A5") (pinfunction "A5_A5") (pintype "passive"))
      (node (ref "X3") (pin "A5") (pinfunction "A5_A5") (pintype "passive"))
      (node (ref "X4") (pin "A5") (pinfunction "A5_A5") (pintype "passive"))
      (node (ref "X5") (pin "A5") (pinfunction "A5_A5") (pintype "passive"))
      (node (ref "X6") (pin "A5") (pinfunction "A5_A5") (pintype "passive"))
      (node (ref "X7") (pin "A5") (pinfunction "A5_A5") (pintype "passive"))
      (node (ref "X8") (pin "A5") (pinfunction "A5_A5") (pintype "passive"))
      (node (ref "X9") (pin "A5") (pinfunction "A5_A5") (pintype "passive"))
    )
    (net (code "26") (name "/n_RESET") (class "Default")
      (node (ref "X0") (pin "14") (pinfunction "14_14") (pintype "passive"))
      (node (ref "X1") (pin "C31") (pinfunction "C31_C31") (pintype "passive"))
      (node (ref "X10") (pin "C31") (pinfunction "C31_C31") (pintype "passive"))
      (node (ref "X11") (pin "C31") (pinfunction "C31_C31") (pintype "passive"))
      (node (ref "X12") (pin "C31") (pinfunction "C31_C31") (pintype "passive"))
      (node (ref "X2") (pin "C31") (pinfunction "C31_C31") (pintype "passive"))
      (node (ref "X3") (pin "C31") (pinfunction "C31_C31") (pintype "passive"))
      (node (ref "X4") (pin "C31") (pinfunction "C31_C31") (pintype "passive"))
      (node (ref "X5") (pin "C31") (pinfunction "C31_C31") (pintype "passive"))
      (node (ref "X6") (pin "C31") (pinfunction "C31_C31") (pintype "passive"))
      (node (ref "X7") (pin "C31") (pinfunction "C31_C31") (pintype "passive"))
      (node (ref "X8") (pin "C31") (pinfunction "C31_C31") (pintype "passive"))
      (node (ref "X9") (pin "C31") (pinfunction "C31_C31") (pintype "passive"))
    )
    (net (code "27") (name "/stby1") (class "Default")
      (node (ref "X1") (pin "A9") (pinfunction "A9_A9") (pintype "passive"))
      (node (ref "X10") (pin "A9") (pinfunction "A9_A9") (pintype "passive"))
      (node (ref "X11") (pin "A9") (pinfunction "A9_A9") (pintype "passive"))
      (node (ref "X12") (pin "A9") (pinfunction "A9_A9") (pintype "passive"))
      (node (ref "X2") (pin "A9") (pinfunction "A9_A9") (pintype "passive"))
      (node (ref "X3") (pin "A9") (pinfunction "A9_A9") (pintype "passive"))
      (node (ref "X4") (pin "A9") (pinfunction "A9_A9") (pintype "passive"))
      (node (ref "X5") (pin "A9") (pinfunction "A9_A9") (pintype "passive"))
      (node (ref "X6") (pin "A9") (pinfunction "A9_A9") (pintype "passive"))
      (node (ref "X7") (pin "A9") (pinfunction "A9_A9") (pintype "passive"))
      (node (ref "X8") (pin "A9") (pinfunction "A9_A9") (pintype "passive"))
      (node (ref "X9") (pin "A9") (pinfunction "A9_A9") (pintype "passive"))
    )
    (net (code "28") (name "/stby2") (class "Default")
      (node (ref "X0") (pin "18") (pinfunction "18_18") (pintype "passive"))
      (node (ref "X1") (pin "A10") (pinfunction "A10_A10") (pintype "passive"))
      (node (ref "X10") (pin "A10") (pinfunction "A10_A10") (pintype "passive"))
      (node (ref "X11") (pin "A10") (pinfunction "A10_A10") (pintype "passive"))
      (node (ref "X12") (pin "A10") (pinfunction "A10_A10") (pintype "passive"))
      (node (ref "X2") (pin "A10") (pinfunction "A10_A10") (pintype "passive"))
      (node (ref "X3") (pin "A10") (pinfunction "A10_A10") (pintype "passive"))
      (node (ref "X4") (pin "A10") (pinfunction "A10_A10") (pintype "passive"))
      (node (ref "X5") (pin "A10") (pinfunction "A10_A10") (pintype "passive"))
      (node (ref "X6") (pin "A10") (pinfunction "A10_A10") (pintype "passive"))
      (node (ref "X7") (pin "A10") (pinfunction "A10_A10") (pintype "passive"))
      (node (ref "X8") (pin "A10") (pinfunction "A10_A10") (pintype "passive"))
      (node (ref "X9") (pin "A10") (pinfunction "A10_A10") (pintype "passive"))
    )
    (net (code "29") (name "/stby3") (class "Default")
      (node (ref "X0") (pin "19") (pinfunction "19_19") (pintype "passive"))
      (node (ref "X1") (pin "A12") (pinfunction "A12_A12") (pintype "passive"))
      (node (ref "X10") (pin "A12") (pinfunction "A12_A12") (pintype "passive"))
      (node (ref "X11") (pin "A12") (pinfunction "A12_A12") (pintype "passive"))
      (node (ref "X12") (pin "A12") (pinfunction "A12_A12") (pintype "passive"))
      (node (ref "X2") (pin "A12") (pinfunction "A12_A12") (pintype "passive"))
      (node (ref "X3") (pin "A12") (pinfunction "A12_A12") (pintype "passive"))
      (node (ref "X4") (pin "A12") (pinfunction "A12_A12") (pintype "passive"))
      (node (ref "X5") (pin "A12") (pinfunction "A12_A12") (pintype "passive"))
      (node (ref "X6") (pin "A12") (pinfunction "A12_A12") (pintype "passive"))
      (node (ref "X7") (pin "A12") (pinfunction "A12_A12") (pintype "passive"))
      (node (ref "X8") (pin "A12") (pinfunction "A12_A12") (pintype "passive"))
      (node (ref "X9") (pin "A12") (pinfunction "A12_A12") (pintype "passive"))
    )
    (net (code "30") (name "/stby4") (class "Default")
      (node (ref "X0") (pin "20") (pinfunction "20_20") (pintype "passive"))
      (node (ref "X1") (pin "A13") (pinfunction "A13_A13") (pintype "passive"))
      (node (ref "X10") (pin "A13") (pinfunction "A13_A13") (pintype "passive"))
      (node (ref "X11") (pin "A13") (pinfunction "A13_A13") (pintype "passive"))
      (node (ref "X12") (pin "A13") (pinfunction "A13_A13") (pintype "passive"))
      (node (ref "X2") (pin "A13") (pinfunction "A13_A13") (pintype "passive"))
      (node (ref "X3") (pin "A13") (pinfunction "A13_A13") (pintype "passive"))
      (node (ref "X4") (pin "A13") (pinfunction "A13_A13") (pintype "passive"))
      (node (ref "X5") (pin "A13") (pinfunction "A13_A13") (pintype "passive"))
      (node (ref "X6") (pin "A13") (pinfunction "A13_A13") (pintype "passive"))
      (node (ref "X7") (pin "A13") (pinfunction "A13_A13") (pintype "passive"))
      (node (ref "X8") (pin "A13") (pinfunction "A13_A13") (pintype "passive"))
      (node (ref "X9") (pin "A13") (pinfunction "A13_A13") (pintype "passive"))
    )
    (net (code "31") (name "/stby5") (class "Default")
      (node (ref "X1") (pin "A14") (pinfunction "A14_A14") (pintype "passive"))
      (node (ref "X10") (pin "A14") (pinfunction "A14_A14") (pintype "passive"))
      (node (ref "X11") (pin "A14") (pinfunction "A14_A14") (pintype "passive"))
      (node (ref "X12") (pin "A14") (pinfunction "A14_A14") (pintype "passive"))
      (node (ref "X2") (pin "A14") (pinfunction "A14_A14") (pintype "passive"))
      (node (ref "X3") (pin "A14") (pinfunction "A14_A14") (pintype "passive"))
      (node (ref "X4") (pin "A14") (pinfunction "A14_A14") (pintype "passive"))
      (node (ref "X5") (pin "A14") (pinfunction "A14_A14") (pintype "passive"))
      (node (ref "X6") (pin "A14") (pinfunction "A14_A14") (pintype "passive"))
      (node (ref "X7") (pin "A14") (pinfunction "A14_A14") (pintype "passive"))
      (node (ref "X8") (pin "A14") (pinfunction "A14_A14") (pintype "passive"))
      (node (ref "X9") (pin "A14") (pinfunction "A14_A14") (pintype "passive"))
    )
    (net (code "32") (name "/stby6") (class "Default")
      (node (ref "X1") (pin "A15") (pinfunction "A15_A15") (pintype "passive"))
      (node (ref "X10") (pin "A15") (pinfunction "A15_A15") (pintype "passive"))
      (node (ref "X11") (pin "A15") (pinfunction "A15_A15") (pintype "passive"))
      (node (ref "X12") (pin "A15") (pinfunction "A15_A15") (pintype "passive"))
      (node (ref "X2") (pin "A15") (pinfunction "A15_A15") (pintype "passive"))
      (node (ref "X3") (pin "A15") (pinfunction "A15_A15") (pintype "passive"))
      (node (ref "X4") (pin "A15") (pinfunction "A15_A15") (pintype "passive"))
      (node (ref "X5") (pin "A15") (pinfunction "A15_A15") (pintype "passive"))
      (node (ref "X6") (pin "A15") (pinfunction "A15_A15") (pintype "passive"))
      (node (ref "X7") (pin "A15") (pinfunction "A15_A15") (pintype "passive"))
      (node (ref "X8") (pin "A15") (pinfunction "A15_A15") (pintype "passive"))
      (node (ref "X9") (pin "A15") (pinfunction "A15_A15") (pintype "passive"))
    )
    (net (code "33") (name "/stby7") (class "Default")
      (node (ref "X1") (pin "A16") (pinfunction "A16_A16") (pintype "passive"))
      (node (ref "X10") (pin "A16") (pinfunction "A16_A16") (pintype "passive"))
      (node (ref "X11") (pin "A16") (pinfunction "A16_A16") (pintype "passive"))
      (node (ref "X12") (pin "A16") (pinfunction "A16_A16") (pintype "passive"))
      (node (ref "X2") (pin "A16") (pinfunction "A16_A16") (pintype "passive"))
      (node (ref "X3") (pin "A16") (pinfunction "A16_A16") (pintype "passive"))
      (node (ref "X4") (pin "A16") (pinfunction "A16_A16") (pintype "passive"))
      (node (ref "X5") (pin "A16") (pinfunction "A16_A16") (pintype "passive"))
      (node (ref "X6") (pin "A16") (pinfunction "A16_A16") (pintype "passive"))
      (node (ref "X7") (pin "A16") (pinfunction "A16_A16") (pintype "passive"))
      (node (ref "X8") (pin "A16") (pinfunction "A16_A16") (pintype "passive"))
      (node (ref "X9") (pin "A16") (pinfunction "A16_A16") (pintype "passive"))
    )
    (net (code "34") (name "/stby8") (class "Default")
      (node (ref "X1") (pin "A17") (pinfunction "A17_A17") (pintype "passive"))
      (node (ref "X10") (pin "A17") (pinfunction "A17_A17") (pintype "passive"))
      (node (ref "X11") (pin "A17") (pinfunction "A17_A17") (pintype "passive"))
      (node (ref "X12") (pin "A17") (pinfunction "A17_A17") (pintype "passive"))
      (node (ref "X2") (pin "A17") (pinfunction "A17_A17") (pintype "passive"))
      (node (ref "X3") (pin "A17") (pinfunction "A17_A17") (pintype "passive"))
      (node (ref "X4") (pin "A17") (pinfunction "A17_A17") (pintype "passive"))
      (node (ref "X5") (pin "A17") (pinfunction "A17_A17") (pintype "passive"))
      (node (ref "X6") (pin "A17") (pinfunction "A17_A17") (pintype "passive"))
      (node (ref "X7") (pin "A17") (pinfunction "A17_A17") (pintype "passive"))
      (node (ref "X8") (pin "A17") (pinfunction "A17_A17") (pintype "passive"))
      (node (ref "X9") (pin "A17") (pinfunction "A17_A17") (pintype "passive"))
    )
    (net (code "35") (name "/stby9") (class "Default")
      (node (ref "X1") (pin "A19") (pinfunction "A19_A19") (pintype "passive"))
      (node (ref "X10") (pin "A19") (pinfunction "A19_A19") (pintype "passive"))
      (node (ref "X11") (pin "A19") (pinfunction "A19_A19") (pintype "passive"))
      (node (ref "X12") (pin "A19") (pinfunction "A19_A19") (pintype "passive"))
      (node (ref "X2") (pin "A19") (pinfunction "A19_A19") (pintype "passive"))
      (node (ref "X3") (pin "A19") (pinfunction "A19_A19") (pintype "passive"))
      (node (ref "X4") (pin "A19") (pinfunction "A19_A19") (pintype "passive"))
      (node (ref "X5") (pin "A19") (pinfunction "A19_A19") (pintype "passive"))
      (node (ref "X6") (pin "A19") (pinfunction "A19_A19") (pintype "passive"))
      (node (ref "X7") (pin "A19") (pinfunction "A19_A19") (pintype "passive"))
      (node (ref "X8") (pin "A19") (pinfunction "A19_A19") (pintype "passive"))
      (node (ref "X9") (pin "A19") (pinfunction "A19_A19") (pintype "passive"))
    )
    (net (code "36") (name "/stby10") (class "Default")
      (node (ref "X1") (pin "A20") (pinfunction "A20_A20") (pintype "passive"))
      (node (ref "X10") (pin "A20") (pinfunction "A20_A20") (pintype "passive"))
      (node (ref "X11") (pin "A20") (pinfunction "A20_A20") (pintype "passive"))
      (node (ref "X12") (pin "A20") (pinfunction "A20_A20") (pintype "passive"))
      (node (ref "X2") (pin "A20") (pinfunction "A20_A20") (pintype "passive"))
      (node (ref "X3") (pin "A20") (pinfunction "A20_A20") (pintype "passive"))
      (node (ref "X4") (pin "A20") (pinfunction "A20_A20") (pintype "passive"))
      (node (ref "X5") (pin "A20") (pinfunction "A20_A20") (pintype "passive"))
      (node (ref "X6") (pin "A20") (pinfunction "A20_A20") (pintype "passive"))
      (node (ref "X7") (pin "A20") (pinfunction "A20_A20") (pintype "passive"))
      (node (ref "X8") (pin "A20") (pinfunction "A20_A20") (pintype "passive"))
      (node (ref "X9") (pin "A20") (pinfunction "A20_A20") (pintype "passive"))
    )
    (net (code "37") (name "/stby11") (class "Default")
      (node (ref "X1") (pin "A21") (pinfunction "A21_A21") (pintype "passive"))
      (node (ref "X10") (pin "A21") (pinfunction "A21_A21") (pintype "passive"))
      (node (ref "X11") (pin "A21") (pinfunction "A21_A21") (pintype "passive"))
      (node (ref "X12") (pin "A21") (pinfunction "A21_A21") (pintype "passive"))
      (node (ref "X2") (pin "A21") (pinfunction "A21_A21") (pintype "passive"))
      (node (ref "X3") (pin "A21") (pinfunction "A21_A21") (pintype "passive"))
      (node (ref "X4") (pin "A21") (pinfunction "A21_A21") (pintype "passive"))
      (node (ref "X5") (pin "A21") (pinfunction "A21_A21") (pintype "passive"))
      (node (ref "X6") (pin "A21") (pinfunction "A21_A21") (pintype "passive"))
      (node (ref "X7") (pin "A21") (pinfunction "A21_A21") (pintype "passive"))
      (node (ref "X8") (pin "A21") (pinfunction "A21_A21") (pintype "passive"))
      (node (ref "X9") (pin "A21") (pinfunction "A21_A21") (pintype "passive"))
    )
    (net (code "38") (name "/stby12") (class "Default")
      (node (ref "X1") (pin "A22") (pinfunction "A22_A22") (pintype "passive"))
      (node (ref "X10") (pin "A22") (pinfunction "A22_A22") (pintype "passive"))
      (node (ref "X11") (pin "A22") (pinfunction "A22_A22") (pintype "passive"))
      (node (ref "X12") (pin "A22") (pinfunction "A22_A22") (pintype "passive"))
      (node (ref "X2") (pin "A22") (pinfunction "A22_A22") (pintype "passive"))
      (node (ref "X3") (pin "A22") (pinfunction "A22_A22") (pintype "passive"))
      (node (ref "X4") (pin "A22") (pinfunction "A22_A22") (pintype "passive"))
      (node (ref "X5") (pin "A22") (pinfunction "A22_A22") (pintype "passive"))
      (node (ref "X6") (pin "A22") (pinfunction "A22_A22") (pintype "passive"))
      (node (ref "X7") (pin "A22") (pinfunction "A22_A22") (pintype "passive"))
      (node (ref "X8") (pin "A22") (pinfunction "A22_A22") (pintype "passive"))
      (node (ref "X9") (pin "A22") (pinfunction "A22_A22") (pintype "passive"))
    )
    (net (code "39") (name "/stby13") (class "Default")
      (node (ref "X1") (pin "A23") (pinfunction "A23_A23") (pintype "passive"))
      (node (ref "X10") (pin "A23") (pinfunction "A23_A23") (pintype "passive"))
      (node (ref "X11") (pin "A23") (pinfunction "A23_A23") (pintype "passive"))
      (node (ref "X12") (pin "A23") (pinfunction "A23_A23") (pintype "passive"))
      (node (ref "X2") (pin "A23") (pinfunction "A23_A23") (pintype "passive"))
      (node (ref "X3") (pin "A23") (pinfunction "A23_A23") (pintype "passive"))
      (node (ref "X4") (pin "A23") (pinfunction "A23_A23") (pintype "passive"))
      (node (ref "X5") (pin "A23") (pinfunction "A23_A23") (pintype "passive"))
      (node (ref "X6") (pin "A23") (pinfunction "A23_A23") (pintype "passive"))
      (node (ref "X7") (pin "A23") (pinfunction "A23_A23") (pintype "passive"))
      (node (ref "X8") (pin "A23") (pinfunction "A23_A23") (pintype "passive"))
      (node (ref "X9") (pin "A23") (pinfunction "A23_A23") (pintype "passive"))
    )
    (net (code "40") (name "/stby14") (class "Default")
      (node (ref "X1") (pin "A24") (pinfunction "A24_A24") (pintype "passive"))
      (node (ref "X10") (pin "A24") (pinfunction "A24_A24") (pintype "passive"))
      (node (ref "X11") (pin "A24") (pinfunction "A24_A24") (pintype "passive"))
      (node (ref "X12") (pin "A24") (pinfunction "A24_A24") (pintype "passive"))
      (node (ref "X2") (pin "A24") (pinfunction "A24_A24") (pintype "passive"))
      (node (ref "X3") (pin "A24") (pinfunction "A24_A24") (pintype "passive"))
      (node (ref "X4") (pin "A24") (pinfunction "A24_A24") (pintype "passive"))
      (node (ref "X5") (pin "A24") (pinfunction "A24_A24") (pintype "passive"))
      (node (ref "X6") (pin "A24") (pinfunction "A24_A24") (pintype "passive"))
      (node (ref "X7") (pin "A24") (pinfunction "A24_A24") (pintype "passive"))
      (node (ref "X8") (pin "A24") (pinfunction "A24_A24") (pintype "passive"))
      (node (ref "X9") (pin "A24") (pinfunction "A24_A24") (pintype "passive"))
    )
    (net (code "41") (name "/stby15") (class "Default")
      (node (ref "X1") (pin "A26") (pinfunction "A26_A26") (pintype "passive"))
      (node (ref "X10") (pin "A26") (pinfunction "A26_A26") (pintype "passive"))
      (node (ref "X11") (pin "A26") (pinfunction "A26_A26") (pintype "passive"))
      (node (ref "X12") (pin "A26") (pinfunction "A26_A26") (pintype "passive"))
      (node (ref "X2") (pin "A26") (pinfunction "A26_A26") (pintype "passive"))
      (node (ref "X3") (pin "A26") (pinfunction "A26_A26") (pintype "passive"))
      (node (ref "X4") (pin "A26") (pinfunction "A26_A26") (pintype "passive"))
      (node (ref "X5") (pin "A26") (pinfunction "A26_A26") (pintype "passive"))
      (node (ref "X6") (pin "A26") (pinfunction "A26_A26") (pintype "passive"))
      (node (ref "X7") (pin "A26") (pinfunction "A26_A26") (pintype "passive"))
      (node (ref "X8") (pin "A26") (pinfunction "A26_A26") (pintype "passive"))
      (node (ref "X9") (pin "A26") (pinfunction "A26_A26") (pintype "passive"))
    )
    (net (code "42") (name "/stby16") (class "Default")
      (node (ref "X1") (pin "A27") (pinfunction "A27_A27") (pintype "passive"))
      (node (ref "X10") (pin "A27") (pinfunction "A27_A27") (pintype "passive"))
      (node (ref "X11") (pin "A27") (pinfunction "A27_A27") (pintype "passive"))
      (node (ref "X12") (pin "A27") (pinfunction "A27_A27") (pintype "passive"))
      (node (ref "X2") (pin "A27") (pinfunction "A27_A27") (pintype "passive"))
      (node (ref "X3") (pin "A27") (pinfunction "A27_A27") (pintype "passive"))
      (node (ref "X4") (pin "A27") (pinfunction "A27_A27") (pintype "passive"))
      (node (ref "X5") (pin "A27") (pinfunction "A27_A27") (pintype "passive"))
      (node (ref "X6") (pin "A27") (pinfunction "A27_A27") (pintype "passive"))
      (node (ref "X7") (pin "A27") (pinfunction "A27_A27") (pintype "passive"))
      (node (ref "X8") (pin "A27") (pinfunction "A27_A27") (pintype "passive"))
      (node (ref "X9") (pin "A27") (pinfunction "A27_A27") (pintype "passive"))
    )
    (net (code "43") (name "/stby17") (class "Default")
      (node (ref "X1") (pin "A28") (pinfunction "A28_A28") (pintype "passive"))
      (node (ref "X10") (pin "A28") (pinfunction "A28_A28") (pintype "passive"))
      (node (ref "X11") (pin "A28") (pinfunction "A28_A28") (pintype "passive"))
      (node (ref "X12") (pin "A28") (pinfunction "A28_A28") (pintype "passive"))
      (node (ref "X2") (pin "A28") (pinfunction "A28_A28") (pintype "passive"))
      (node (ref "X3") (pin "A28") (pinfunction "A28_A28") (pintype "passive"))
      (node (ref "X4") (pin "A28") (pinfunction "A28_A28") (pintype "passive"))
      (node (ref "X5") (pin "A28") (pinfunction "A28_A28") (pintype "passive"))
      (node (ref "X6") (pin "A28") (pinfunction "A28_A28") (pintype "passive"))
      (node (ref "X7") (pin "A28") (pinfunction "A28_A28") (pintype "passive"))
      (node (ref "X8") (pin "A28") (pinfunction "A28_A28") (pintype "passive"))
      (node (ref "X9") (pin "A28") (pinfunction "A28_A28") (pintype "passive"))
    )
    (net (code "44") (name "/time") (class "Default")
      (node (ref "X0") (pin "17") (pinfunction "17_17") (pintype "passive"))
      (node (ref "X1") (pin "A29") (pinfunction "A29_A29") (pintype "passive"))
      (node (ref "X10") (pin "A29") (pinfunction "A29_A29") (pintype "passive"))
      (node (ref "X11") (pin "A29") (pinfunction "A29_A29") (pintype "passive"))
      (node (ref "X12") (pin "A29") (pinfunction "A29_A29") (pintype "passive"))
      (node (ref "X2") (pin "A29") (pinfunction "A29_A29") (pintype "passive"))
      (node (ref "X3") (pin "A29") (pinfunction "A29_A29") (pintype "passive"))
      (node (ref "X4") (pin "A29") (pinfunction "A29_A29") (pintype "passive"))
      (node (ref "X5") (pin "A29") (pinfunction "A29_A29") (pintype "passive"))
      (node (ref "X6") (pin "A29") (pinfunction "A29_A29") (pintype "passive"))
      (node (ref "X7") (pin "A29") (pinfunction "A29_A29") (pintype "passive"))
      (node (ref "X8") (pin "A29") (pinfunction "A29_A29") (pintype "passive"))
      (node (ref "X9") (pin "A29") (pinfunction "A29_A29") (pintype "passive"))
    )
    (net (code "45") (name "GND") (class "Default")
      (node (ref "R1") (pin "2") (pinfunction "2_2") (pintype "passive"))
      (node (ref "X0") (pin "5") (pinfunction "5_5") (pintype "passive"))
      (node (ref "X0") (pin "6") (pinfunction "6_6") (pintype "passive"))
      (node (ref "X0") (pin "7") (pinfunction "7_7") (pintype "passive"))
      (node (ref "X0") (pin "8") (pinfunction "8_8") (pintype "passive"))
      (node (ref "X1") (pin "A11") (pinfunction "A11_A11") (pintype "passive"))
      (node (ref "X1") (pin "A18") (pinfunction "A18_A18") (pintype "passive"))
      (node (ref "X1") (pin "A25") (pinfunction "A25_A25") (pintype "passive"))
      (node (ref "X1") (pin "A3") (pinfunction "A3_A3") (pintype "passive"))
      (node (ref "X1") (pin "A32") (pinfunction "A32_A32") (pintype "passive"))
      (node (ref "X1") (pin "A4") (pinfunction "A4_A4") (pintype "passive"))
      (node (ref "X1") (pin "B11") (pinfunction "B11_B11") (pintype "passive"))
      (node (ref "X1") (pin "B18") (pinfunction "B18_B18") (pintype "passive"))
      (node (ref "X1") (pin "B25") (pinfunction "B25_B25") (pintype "passive"))
      (node (ref "X1") (pin "B3") (pinfunction "B3_B3") (pintype "passive"))
      (node (ref "X1") (pin "B32") (pinfunction "B32_B32") (pintype "passive"))
      (node (ref "X1") (pin "B4") (pinfunction "B4_B4") (pintype "passive"))
      (node (ref "X1") (pin "C11") (pinfunction "C11_C11") (pintype "passive"))
      (node (ref "X1") (pin "C18") (pinfunction "C18_C18") (pintype "passive"))
      (node (ref "X1") (pin "C25") (pinfunction "C25_C25") (pintype "passive"))
      (node (ref "X1") (pin "C3") (pinfunction "C3_C3") (pintype "passive"))
      (node (ref "X1") (pin "C32") (pinfunction "C32_C32") (pintype "passive"))
      (node (ref "X1") (pin "C4") (pinfunction "C4_C4") (pintype "passive"))
      (node (ref "X10") (pin "A11") (pinfunction "A11_A11") (pintype "passive"))
      (node (ref "X10") (pin "A18") (pinfunction "A18_A18") (pintype "passive"))
      (node (ref "X10") (pin "A25") (pinfunction "A25_A25") (pintype "passive"))
      (node (ref "X10") (pin "A3") (pinfunction "A3_A3") (pintype "passive"))
      (node (ref "X10") (pin "A32") (pinfunction "A32_A32") (pintype "passive"))
      (node (ref "X10") (pin "A4") (pinfunction "A4_A4") (pintype "passive"))
      (node (ref "X10") (pin "B11") (pinfunction "B11_B11") (pintype "passive"))
      (node (ref "X10") (pin "B18") (pinfunction "B18_B18") (pintype "passive"))
      (node (ref "X10") (pin "B25") (pinfunction "B25_B25") (pintype "passive"))
      (node (ref "X10") (pin "B3") (pinfunction "B3_B3") (pintype "passive"))
      (node (ref "X10") (pin "B32") (pinfunction "B32_B32") (pintype "passive"))
      (node (ref "X10") (pin "B4") (pinfunction "B4_B4") (pintype "passive"))
      (node (ref "X10") (pin "C11") (pinfunction "C11_C11") (pintype "passive"))
      (node (ref "X10") (pin "C18") (pinfunction "C18_C18") (pintype "passive"))
      (node (ref "X10") (pin "C25") (pinfunction "C25_C25") (pintype "passive"))
      (node (ref "X10") (pin "C3") (pinfunction "C3_C3") (pintype "passive"))
      (node (ref "X10") (pin "C32") (pinfunction "C32_C32") (pintype "passive"))
      (node (ref "X10") (pin "C4") (pinfunction "C4_C4") (pintype "passive"))
      (node (ref "X11") (pin "A11") (pinfunction "A11_A11") (pintype "passive"))
      (node (ref "X11") (pin "A18") (pinfunction "A18_A18") (pintype "passive"))
      (node (ref "X11") (pin "A25") (pinfunction "A25_A25") (pintype "passive"))
      (node (ref "X11") (pin "A3") (pinfunction "A3_A3") (pintype "passive"))
      (node (ref "X11") (pin "A32") (pinfunction "A32_A32") (pintype "passive"))
      (node (ref "X11") (pin "A4") (pinfunction "A4_A4") (pintype "passive"))
      (node (ref "X11") (pin "B11") (pinfunction "B11_B11") (pintype "passive"))
      (node (ref "X11") (pin "B18") (pinfunction "B18_B18") (pintype "passive"))
      (node (ref "X11") (pin "B25") (pinfunction "B25_B25") (pintype "passive"))
      (node (ref "X11") (pin "B3") (pinfunction "B3_B3") (pintype "passive"))
      (node (ref "X11") (pin "B32") (pinfunction "B32_B32") (pintype "passive"))
      (node (ref "X11") (pin "B4") (pinfunction "B4_B4") (pintype "passive"))
      (node (ref "X11") (pin "C11") (pinfunction "C11_C11") (pintype "passive"))
      (node (ref "X11") (pin "C18") (pinfunction "C18_C18") (pintype "passive"))
      (node (ref "X11") (pin "C25") (pinfunction "C25_C25") (pintype "passive"))
      (node (ref "X11") (pin "C3") (pinfunction "C3_C3") (pintype "passive"))
      (node (ref "X11") (pin "C32") (pinfunction "C32_C32") (pintype "passive"))
      (node (ref "X11") (pin "C4") (pinfunction "C4_C4") (pintype "passive"))
      (node (ref "X12") (pin "A11") (pinfunction "A11_A11") (pintype "passive"))
      (node (ref "X12") (pin "A18") (pinfunction "A18_A18") (pintype "passive"))
      (node (ref "X12") (pin "A25") (pinfunction "A25_A25") (pintype "passive"))
      (node (ref "X12") (pin "A3") (pinfunction "A3_A3") (pintype "passive"))
      (node (ref "X12") (pin "A32") (pinfunction "A32_A32") (pintype "passive"))
      (node (ref "X12") (pin "A4") (pinfunction "A4_A4") (pintype "passive"))
      (node (ref "X12") (pin "B11") (pinfunction "B11_B11") (pintype "passive"))
      (node (ref "X12") (pin "B18") (pinfunction "B18_B18") (pintype "passive"))
      (node (ref "X12") (pin "B25") (pinfunction "B25_B25") (pintype "passive"))
      (node (ref "X12") (pin "B3") (pinfunction "B3_B3") (pintype "passive"))
      (node (ref "X12") (pin "B32") (pinfunction "B32_B32") (pintype "passive"))
      (node (ref "X12") (pin "B4") (pinfunction "B4_B4") (pintype "passive"))
      (node (ref "X12") (pin "C11") (pinfunction "C11_C11") (pintype "passive"))
      (node (ref "X12") (pin "C18") (pinfunction "C18_C18") (pintype "passive"))
      (node (ref "X12") (pin "C25") (pinfunction "C25_C25") (pintype "passive"))
      (node (ref "X12") (pin "C3") (pinfunction "C3_C3") (pintype "passive"))
      (node (ref "X12") (pin "C32") (pinfunction "C32_C32") (pintype "passive"))
      (node (ref "X12") (pin "C4") (pinfunction "C4_C4") (pintype "passive"))
      (node (ref "X2") (pin "A11") (pinfunction "A11_A11") (pintype "passive"))
      (node (ref "X2") (pin "A18") (pinfunction "A18_A18") (pintype "passive"))
      (node (ref "X2") (pin "A25") (pinfunction "A25_A25") (pintype "passive"))
      (node (ref "X2") (pin "A3") (pinfunction "A3_A3") (pintype "passive"))
      (node (ref "X2") (pin "A32") (pinfunction "A32_A32") (pintype "passive"))
      (node (ref "X2") (pin "A4") (pinfunction "A4_A4") (pintype "passive"))
      (node (ref "X2") (pin "B11") (pinfunction "B11_B11") (pintype "passive"))
      (node (ref "X2") (pin "B18") (pinfunction "B18_B18") (pintype "passive"))
      (node (ref "X2") (pin "B25") (pinfunction "B25_B25") (pintype "passive"))
      (node (ref "X2") (pin "B3") (pinfunction "B3_B3") (pintype "passive"))
      (node (ref "X2") (pin "B32") (pinfunction "B32_B32") (pintype "passive"))
      (node (ref "X2") (pin "B4") (pinfunction "B4_B4") (pintype "passive"))
      (node (ref "X2") (pin "C11") (pinfunction "C11_C11") (pintype "passive"))
      (node (ref "X2") (pin "C18") (pinfunction "C18_C18") (pintype "passive"))
      (node (ref "X2") (pin "C25") (pinfunction "C25_C25") (pintype "passive"))
      (node (ref "X2") (pin "C3") (pinfunction "C3_C3") (pintype "passive"))
      (node (ref "X2") (pin "C32") (pinfunction "C32_C32") (pintype "passive"))
      (node (ref "X2") (pin "C4") (pinfunction "C4_C4") (pintype "passive"))
      (node (ref "X3") (pin "A11") (pinfunction "A11_A11") (pintype "passive"))
      (node (ref "X3") (pin "A18") (pinfunction "A18_A18") (pintype "passive"))
      (node (ref "X3") (pin "A25") (pinfunction "A25_A25") (pintype "passive"))
      (node (ref "X3") (pin "A3") (pinfunction "A3_A3") (pintype "passive"))
      (node (ref "X3") (pin "A32") (pinfunction "A32_A32") (pintype "passive"))
      (node (ref "X3") (pin "A4") (pinfunction "A4_A4") (pintype "passive"))
      (node (ref "X3") (pin "B11") (pinfunction "B11_B11") (pintype "passive"))
      (node (ref "X3") (pin "B18") (pinfunction "B18_B18") (pintype "passive"))
      (node (ref "X3") (pin "B25") (pinfunction "B25_B25") (pintype "passive"))
      (node (ref "X3") (pin "B3") (pinfunction "B3_B3") (pintype "passive"))
      (node (ref "X3") (pin "B32") (pinfunction "B32_B32") (pintype "passive"))
      (node (ref "X3") (pin "B4") (pinfunction "B4_B4") (pintype "passive"))
      (node (ref "X3") (pin "C11") (pinfunction "C11_C11") (pintype "passive"))
      (node (ref "X3") (pin "C18") (pinfunction "C18_C18") (pintype "passive"))
      (node (ref "X3") (pin "C25") (pinfunction "C25_C25") (pintype "passive"))
      (node (ref "X3") (pin "C3") (pinfunction "C3_C3") (pintype "passive"))
      (node (ref "X3") (pin "C32") (pinfunction "C32_C32") (pintype "passive"))
      (node (ref "X3") (pin "C4") (pinfunction "C4_C4") (pintype "passive"))
      (node (ref "X4") (pin "A11") (pinfunction "A11_A11") (pintype "passive"))
      (node (ref "X4") (pin "A18") (pinfunction "A18_A18") (pintype "passive"))
      (node (ref "X4") (pin "A25") (pinfunction "A25_A25") (pintype "passive"))
      (node (ref "X4") (pin "A3") (pinfunction "A3_A3") (pintype "passive"))
      (node (ref "X4") (pin "A32") (pinfunction "A32_A32") (pintype "passive"))
      (node (ref "X4") (pin "A4") (pinfunction "A4_A4") (pintype "passive"))
      (node (ref "X4") (pin "B11") (pinfunction "B11_B11") (pintype "passive"))
      (node (ref "X4") (pin "B18") (pinfunction "B18_B18") (pintype "passive"))
      (node (ref "X4") (pin "B25") (pinfunction "B25_B25") (pintype "passive"))
      (node (ref "X4") (pin "B3") (pinfunction "B3_B3") (pintype "passive"))
      (node (ref "X4") (pin "B32") (pinfunction "B32_B32") (pintype "passive"))
      (node (ref "X4") (pin "B4") (pinfunction "B4_B4") (pintype "passive"))
      (node (ref "X4") (pin "C11") (pinfunction "C11_C11") (pintype "passive"))
      (node (ref "X4") (pin "C18") (pinfunction "C18_C18") (pintype "passive"))
      (node (ref "X4") (pin "C25") (pinfunction "C25_C25") (pintype "passive"))
      (node (ref "X4") (pin "C3") (pinfunction "C3_C3") (pintype "passive"))
      (node (ref "X4") (pin "C32") (pinfunction "C32_C32") (pintype "passive"))
      (node (ref "X4") (pin "C4") (pinfunction "C4_C4") (pintype "passive"))
      (node (ref "X5") (pin "A11") (pinfunction "A11_A11") (pintype "passive"))
      (node (ref "X5") (pin "A18") (pinfunction "A18_A18") (pintype "passive"))
      (node (ref "X5") (pin "A25") (pinfunction "A25_A25") (pintype "passive"))
      (node (ref "X5") (pin "A3") (pinfunction "A3_A3") (pintype "passive"))
      (node (ref "X5") (pin "A32") (pinfunction "A32_A32") (pintype "passive"))
      (node (ref "X5") (pin "A4") (pinfunction "A4_A4") (pintype "passive"))
      (node (ref "X5") (pin "B11") (pinfunction "B11_B11") (pintype "passive"))
      (node (ref "X5") (pin "B18") (pinfunction "B18_B18") (pintype "passive"))
      (node (ref "X5") (pin "B25") (pinfunction "B25_B25") (pintype "passive"))
      (node (ref "X5") (pin "B3") (pinfunction "B3_B3") (pintype "passive"))
      (node (ref "X5") (pin "B32") (pinfunction "B32_B32") (pintype "passive"))
      (node (ref "X5") (pin "B4") (pinfunction "B4_B4") (pintype "passive"))
      (node (ref "X5") (pin "C11") (pinfunction "C11_C11") (pintype "passive"))
      (node (ref "X5") (pin "C18") (pinfunction "C18_C18") (pintype "passive"))
      (node (ref "X5") (pin "C25") (pinfunction "C25_C25") (pintype "passive"))
      (node (ref "X5") (pin "C3") (pinfunction "C3_C3") (pintype "passive"))
      (node (ref "X5") (pin "C32") (pinfunction "C32_C32") (pintype "passive"))
      (node (ref "X5") (pin "C4") (pinfunction "C4_C4") (pintype "passive"))
      (node (ref "X6") (pin "A11") (pinfunction "A11_A11") (pintype "passive"))
      (node (ref "X6") (pin "A18") (pinfunction "A18_A18") (pintype "passive"))
      (node (ref "X6") (pin "A25") (pinfunction "A25_A25") (pintype "passive"))
      (node (ref "X6") (pin "A3") (pinfunction "A3_A3") (pintype "passive"))
      (node (ref "X6") (pin "A32") (pinfunction "A32_A32") (pintype "passive"))
      (node (ref "X6") (pin "A4") (pinfunction "A4_A4") (pintype "passive"))
      (node (ref "X6") (pin "B11") (pinfunction "B11_B11") (pintype "passive"))
      (node (ref "X6") (pin "B18") (pinfunction "B18_B18") (pintype "passive"))
      (node (ref "X6") (pin "B25") (pinfunction "B25_B25") (pintype "passive"))
      (node (ref "X6") (pin "B3") (pinfunction "B3_B3") (pintype "passive"))
      (node (ref "X6") (pin "B32") (pinfunction "B32_B32") (pintype "passive"))
      (node (ref "X6") (pin "B4") (pinfunction "B4_B4") (pintype "passive"))
      (node (ref "X6") (pin "C11") (pinfunction "C11_C11") (pintype "passive"))
      (node (ref "X6") (pin "C18") (pinfunction "C18_C18") (pintype "passive"))
      (node (ref "X6") (pin "C25") (pinfunction "C25_C25") (pintype "passive"))
      (node (ref "X6") (pin "C3") (pinfunction "C3_C3") (pintype "passive"))
      (node (ref "X6") (pin "C32") (pinfunction "C32_C32") (pintype "passive"))
      (node (ref "X6") (pin "C4") (pinfunction "C4_C4") (pintype "passive"))
      (node (ref "X7") (pin "A11") (pinfunction "A11_A11") (pintype "passive"))
      (node (ref "X7") (pin "A18") (pinfunction "A18_A18") (pintype "passive"))
      (node (ref "X7") (pin "A25") (pinfunction "A25_A25") (pintype "passive"))
      (node (ref "X7") (pin "A3") (pinfunction "A3_A3") (pintype "passive"))
      (node (ref "X7") (pin "A4") (pinfunction "A4_A4") (pintype "passive"))
      (node (ref "X7") (pin "B11") (pinfunction "B11_B11") (pintype "passive"))
      (node (ref "X7") (pin "B18") (pinfunction "B18_B18") (pintype "passive"))
      (node (ref "X7") (pin "B25") (pinfunction "B25_B25") (pintype "passive"))
      (node (ref "X7") (pin "B3") (pinfunction "B3_B3") (pintype "passive"))
      (node (ref "X7") (pin "B30") (pinfunction "B30_B30") (pintype "passive"))
      (node (ref "X7") (pin "B4") (pinfunction "B4_B4") (pintype "passive"))
      (node (ref "X7") (pin "C11") (pinfunction "C11_C11") (pintype "passive"))
      (node (ref "X7") (pin "C18") (pinfunction "C18_C18") (pintype "passive"))
      (node (ref "X7") (pin "C25") (pinfunction "C25_C25") (pintype "passive"))
      (node (ref "X7") (pin "C3") (pinfunction "C3_C3") (pintype "passive"))
      (node (ref "X7") (pin "C4") (pinfunction "C4_C4") (pintype "passive"))
      (node (ref "X8") (pin "A11") (pinfunction "A11_A11") (pintype "passive"))
      (node (ref "X8") (pin "A18") (pinfunction "A18_A18") (pintype "passive"))
      (node (ref "X8") (pin "A25") (pinfunction "A25_A25") (pintype "passive"))
      (node (ref "X8") (pin "A3") (pinfunction "A3_A3") (pintype "passive"))
      (node (ref "X8") (pin "A4") (pinfunction "A4_A4") (pintype "passive"))
      (node (ref "X8") (pin "B11") (pinfunction "B11_B11") (pintype "passive"))
      (node (ref "X8") (pin "B18") (pinfunction "B18_B18") (pintype "passive"))
      (node (ref "X8") (pin "B25") (pinfunction "B25_B25") (pintype "passive"))
      (node (ref "X8") (pin "B3") (pinfunction "B3_B3") (pintype "passive"))
      (node (ref "X8") (pin "B30") (pinfunction "B30_B30") (pintype "passive"))
      (node (ref "X8") (pin "B4") (pinfunction "B4_B4") (pintype "passive"))
      (node (ref "X8") (pin "C11") (pinfunction "C11_C11") (pintype "passive"))
      (node (ref "X8") (pin "C18") (pinfunction "C18_C18") (pintype "passive"))
      (node (ref "X8") (pin "C25") (pinfunction "C25_C25") (pintype "passive"))
      (node (ref "X8") (pin "C3") (pinfunction "C3_C3") (pintype "passive"))
      (node (ref "X8") (pin "C4") (pinfunction "C4_C4") (pintype "passive"))
      (node (ref "X9") (pin "A11") (pinfunction "A11_A11") (pintype "passive"))
      (node (ref "X9") (pin "A18") (pinfunction "A18_A18") (pintype "passive"))
      (node (ref "X9") (pin "A25") (pinfunction "A25_A25") (pintype "passive"))
      (node (ref "X9") (pin "A3") (pinfunction "A3_A3") (pintype "passive"))
      (node (ref "X9") (pin "A32") (pinfunction "A32_A32") (pintype "passive"))
      (node (ref "X9") (pin "A4") (pinfunction "A4_A4") (pintype "passive"))
      (node (ref "X9") (pin "B11") (pinfunction "B11_B11") (pintype "passive"))
      (node (ref "X9") (pin "B18") (pinfunction "B18_B18") (pintype "passive"))
      (node (ref "X9") (pin "B25") (pinfunction "B25_B25") (pintype "passive"))
      (node (ref "X9") (pin "B3") (pinfunction "B3_B3") (pintype "passive"))
      (node (ref "X9") (pin "B32") (pinfunction "B32_B32") (pintype "passive"))
      (node (ref "X9") (pin "B4") (pinfunction "B4_B4") (pintype "passive"))
      (node (ref "X9") (pin "C11") (pinfunction "C11_C11") (pintype "passive"))
      (node (ref "X9") (pin "C18") (pinfunction "C18_C18") (pintype "passive"))
      (node (ref "X9") (pin "C25") (pinfunction "C25_C25") (pintype "passive"))
      (node (ref "X9") (pin "C3") (pinfunction "C3_C3") (pintype "passive"))
      (node (ref "X9") (pin "C32") (pinfunction "C32_C32") (pintype "passive"))
      (node (ref "X9") (pin "C4") (pinfunction "C4_C4") (pintype "passive"))
    )
    (net (code "46") (name "PE") (class "Default")
      (node (ref "X7") (pin "A31") (pinfunction "A31_A31") (pintype "passive"))
      (node (ref "X7") (pin "A32") (pinfunction "A32_A32") (pintype "passive"))
      (node (ref "X7") (pin "B31") (pinfunction "B31_B31") (pintype "passive"))
      (node (ref "X7") (pin "B32") (pinfunction "B32_B32") (pintype "passive"))
      (node (ref "X7") (pin "C32") (pinfunction "C32_C32") (pintype "passive"))
      (node (ref "X8") (pin "A31") (pinfunction "A31_A31") (pintype "passive"))
      (node (ref "X8") (pin "A32") (pinfunction "A32_A32") (pintype "passive"))
      (node (ref "X8") (pin "B31") (pinfunction "B31_B31") (pintype "passive"))
      (node (ref "X8") (pin "B32") (pinfunction "B32_B32") (pintype "passive"))
      (node (ref "X8") (pin "C32") (pinfunction "C32_C32") (pintype "passive"))
    )
    (net (code "47") (name "unconnected-(X1-Pad97)") (class "Default")
      (node (ref "X1") (pin "97") (pinfunction "97_97") (pintype "passive"))
    )
    (net (code "48") (name "unconnected-(X1-Pad98)") (class "Default")
      (node (ref "X1") (pin "98") (pinfunction "98_98") (pintype "passive"))
    )
    (net (code "49") (name "unconnected-(X1-PadA31)") (class "Default")
      (node (ref "X1") (pin "A31") (pinfunction "A31_A31") (pintype "passive"))
    )
    (net (code "50") (name "unconnected-(X1-PadB5)") (class "Default")
      (node (ref "X1") (pin "B5") (pinfunction "B5_B5") (pintype "passive"))
    )
    (net (code "51") (name "unconnected-(X1-PadB6)") (class "Default")
      (node (ref "X1") (pin "B6") (pinfunction "B6_B6") (pintype "passive"))
    )
    (net (code "52") (name "unconnected-(X1-PadB7)") (class "Default")
      (node (ref "X1") (pin "B7") (pinfunction "B7_B7") (pintype "passive"))
    )
    (net (code "53") (name "unconnected-(X1-PadB8)") (class "Default")
      (node (ref "X1") (pin "B8") (pinfunction "B8_B8") (pintype "passive"))
    )
    (net (code "54") (name "unconnected-(X1-PadB9)") (class "Default")
      (node (ref "X1") (pin "B9") (pinfunction "B9_B9") (pintype "passive"))
    )
    (net (code "55") (name "unconnected-(X1-PadB10)") (class "Default")
      (node (ref "X1") (pin "B10") (pinfunction "B10_B10") (pintype "passive"))
    )
    (net (code "56") (name "unconnected-(X1-PadB12)") (class "Default")
      (node (ref "X1") (pin "B12") (pinfunction "B12_B12") (pintype "passive"))
    )
    (net (code "57") (name "unconnected-(X1-PadB13)") (class "Default")
      (node (ref "X1") (pin "B13") (pinfunction "B13_B13") (pintype "passive"))
    )
    (net (code "58") (name "unconnected-(X1-PadB14)") (class "Default")
      (node (ref "X1") (pin "B14") (pinfunction "B14_B14") (pintype "passive"))
    )
    (net (code "59") (name "unconnected-(X1-PadB15)") (class "Default")
      (node (ref "X1") (pin "B15") (pinfunction "B15_B15") (pintype "passive"))
    )
    (net (code "60") (name "unconnected-(X1-PadB16)") (class "Default")
      (node (ref "X1") (pin "B16") (pinfunction "B16_B16") (pintype "passive"))
    )
    (net (code "61") (name "unconnected-(X1-PadB17)") (class "Default")
      (node (ref "X1") (pin "B17") (pinfunction "B17_B17") (pintype "passive"))
    )
    (net (code "62") (name "unconnected-(X1-PadB19)") (class "Default")
      (node (ref "X1") (pin "B19") (pinfunction "B19_B19") (pintype "passive"))
    )
    (net (code "63") (name "unconnected-(X1-PadB20)") (class "Default")
      (node (ref "X1") (pin "B20") (pinfunction "B20_B20") (pintype "passive"))
    )
    (net (code "64") (name "unconnected-(X1-PadB21)") (class "Default")
      (node (ref "X1") (pin "B21") (pinfunction "B21_B21") (pintype "passive"))
    )
    (net (code "65") (name "unconnected-(X1-PadB22)") (class "Default")
      (node (ref "X1") (pin "B22") (pinfunction "B22_B22") (pintype "passive"))
    )
    (net (code "66") (name "unconnected-(X1-PadB23)") (class "Default")
      (node (ref "X1") (pin "B23") (pinfunction "B23_B23") (pintype "passive"))
    )
    (net (code "67") (name "unconnected-(X1-PadB24)") (class "Default")
      (node (ref "X1") (pin "B24") (pinfunction "B24_B24") (pintype "passive"))
    )
    (net (code "68") (name "unconnected-(X1-PadB26)") (class "Default")
      (node (ref "X1") (pin "B26") (pinfunction "B26_B26") (pintype "passive"))
    )
    (net (code "69") (name "unconnected-(X1-PadB27)") (class "Default")
      (node (ref "X1") (pin "B27") (pinfunction "B27_B27") (pintype "passive"))
    )
    (net (code "70") (name "unconnected-(X1-PadB28)") (class "Default")
      (node (ref "X1") (pin "B28") (pinfunction "B28_B28") (pintype "passive"))
    )
    (net (code "71") (name "unconnected-(X1-PadB29)") (class "Default")
      (node (ref "X1") (pin "B29") (pinfunction "B29_B29") (pintype "passive"))
    )
    (net (code "72") (name "unconnected-(X1-PadB30)") (class "Default")
      (node (ref "X1") (pin "B30") (pinfunction "B30_B30") (pintype "passive"))
    )
    (net (code "73") (name "unconnected-(X1-PadB31)") (class "Default")
      (node (ref "X1") (pin "B31") (pinfunction "B31_B31") (pintype "passive"))
    )
    (net (code "74") (name "unconnected-(X2-Pad97)") (class "Default")
      (node (ref "X2") (pin "97") (pinfunction "97_97") (pintype "passive"))
    )
    (net (code "75") (name "unconnected-(X2-Pad98)") (class "Default")
      (node (ref "X2") (pin "98") (pinfunction "98_98") (pintype "passive"))
    )
    (net (code "76") (name "unconnected-(X2-PadA31)") (class "Default")
      (node (ref "X2") (pin "A31") (pinfunction "A31_A31") (pintype "passive"))
    )
    (net (code "77") (name "unconnected-(X2-PadB5)") (class "Default")
      (node (ref "X2") (pin "B5") (pinfunction "B5_B5") (pintype "passive"))
    )
    (net (code "78") (name "unconnected-(X2-PadB6)") (class "Default")
      (node (ref "X2") (pin "B6") (pinfunction "B6_B6") (pintype "passive"))
    )
    (net (code "79") (name "unconnected-(X2-PadB7)") (class "Default")
      (node (ref "X2") (pin "B7") (pinfunction "B7_B7") (pintype "passive"))
    )
    (net (code "80") (name "unconnected-(X2-PadB8)") (class "Default")
      (node (ref "X2") (pin "B8") (pinfunction "B8_B8") (pintype "passive"))
    )
    (net (code "81") (name "unconnected-(X2-PadB9)") (class "Default")
      (node (ref "X2") (pin "B9") (pinfunction "B9_B9") (pintype "passive"))
    )
    (net (code "82") (name "unconnected-(X2-PadB10)") (class "Default")
      (node (ref "X2") (pin "B10") (pinfunction "B10_B10") (pintype "passive"))
    )
    (net (code "83") (name "unconnected-(X2-PadB12)") (class "Default")
      (node (ref "X2") (pin "B12") (pinfunction "B12_B12") (pintype "passive"))
    )
    (net (code "84") (name "unconnected-(X2-PadB13)") (class "Default")
      (node (ref "X2") (pin "B13") (pinfunction "B13_B13") (pintype "passive"))
    )
    (net (code "85") (name "unconnected-(X2-PadB14)") (class "Default")
      (node (ref "X2") (pin "B14") (pinfunction "B14_B14") (pintype "passive"))
    )
    (net (code "86") (name "unconnected-(X2-PadB15)") (class "Default")
      (node (ref "X2") (pin "B15") (pinfunction "B15_B15") (pintype "passive"))
    )
    (net (code "87") (name "unconnected-(X2-PadB16)") (class "Default")
      (node (ref "X2") (pin "B16") (pinfunction "B16_B16") (pintype "passive"))
    )
    (net (code "88") (name "unconnected-(X2-PadB17)") (class "Default")
      (node (ref "X2") (pin "B17") (pinfunction "B17_B17") (pintype "passive"))
    )
    (net (code "89") (name "unconnected-(X2-PadB19)") (class "Default")
      (node (ref "X2") (pin "B19") (pinfunction "B19_B19") (pintype "passive"))
    )
    (net (code "90") (name "unconnected-(X2-PadB20)") (class "Default")
      (node (ref "X2") (pin "B20") (pinfunction "B20_B20") (pintype "passive"))
    )
    (net (code "91") (name "unconnected-(X2-PadB21)") (class "Default")
      (node (ref "X2") (pin "B21") (pinfunction "B21_B21") (pintype "passive"))
    )
    (net (code "92") (name "unconnected-(X2-PadB22)") (class "Default")
      (node (ref "X2") (pin "B22") (pinfunction "B22_B22") (pintype "passive"))
    )
    (net (code "93") (name "unconnected-(X2-PadB23)") (class "Default")
      (node (ref "X2") (pin "B23") (pinfunction "B23_B23") (pintype "passive"))
    )
    (net (code "94") (name "unconnected-(X2-PadB24)") (class "Default")
      (node (ref "X2") (pin "B24") (pinfunction "B24_B24") (pintype "passive"))
    )
    (net (code "95") (name "unconnected-(X2-PadB26)") (class "Default")
      (node (ref "X2") (pin "B26") (pinfunction "B26_B26") (pintype "passive"))
    )
    (net (code "96") (name "unconnected-(X2-PadB27)") (class "Default")
      (node (ref "X2") (pin "B27") (pinfunction "B27_B27") (pintype "passive"))
    )
    (net (code "97") (name "unconnected-(X2-PadB28)") (class "Default")
      (node (ref "X2") (pin "B28") (pinfunction "B28_B28") (pintype "passive"))
    )
    (net (code "98") (name "unconnected-(X2-PadB29)") (class "Default")
      (node (ref "X2") (pin "B29") (pinfunction "B29_B29") (pintype "passive"))
    )
    (net (code "99") (name "unconnected-(X2-PadB30)") (class "Default")
      (node (ref "X2") (pin "B30") (pinfunction "B30_B30") (pintype "passive"))
    )
    (net (code "100") (name "unconnected-(X2-PadB31)") (class "Default")
      (node (ref "X2") (pin "B31") (pinfunction "B31_B31") (pintype "passive"))
    )
    (net (code "101") (name "unconnected-(X3-Pad97)") (class "Default")
      (node (ref "X3") (pin "97") (pinfunction "97_97") (pintype "passive"))
    )
    (net (code "102") (name "unconnected-(X3-Pad98)") (class "Default")
      (node (ref "X3") (pin "98") (pinfunction "98_98") (pintype "passive"))
    )
    (net (code "103") (name "unconnected-(X3-PadA31)") (class "Default")
      (node (ref "X3") (pin "A31") (pinfunction "A31_A31") (pintype "passive"))
    )
    (net (code "104") (name "unconnected-(X3-PadB5)") (class "Default")
      (node (ref "X3") (pin "B5") (pinfunction "B5_B5") (pintype "passive"))
    )
    (net (code "105") (name "unconnected-(X3-PadB6)") (class "Default")
      (node (ref "X3") (pin "B6") (pinfunction "B6_B6") (pintype "passive"))
    )
    (net (code "106") (name "unconnected-(X3-PadB7)") (class "Default")
      (node (ref "X3") (pin "B7") (pinfunction "B7_B7") (pintype "passive"))
    )
    (net (code "107") (name "unconnected-(X3-PadB8)") (class "Default")
      (node (ref "X3") (pin "B8") (pinfunction "B8_B8") (pintype "passive"))
    )
    (net (code "108") (name "unconnected-(X3-PadB9)") (class "Default")
      (node (ref "X3") (pin "B9") (pinfunction "B9_B9") (pintype "passive"))
    )
    (net (code "109") (name "unconnected-(X3-PadB10)") (class "Default")
      (node (ref "X3") (pin "B10") (pinfunction "B10_B10") (pintype "passive"))
    )
    (net (code "110") (name "unconnected-(X3-PadB12)") (class "Default")
      (node (ref "X3") (pin "B12") (pinfunction "B12_B12") (pintype "passive"))
    )
    (net (code "111") (name "unconnected-(X3-PadB13)") (class "Default")
      (node (ref "X3") (pin "B13") (pinfunction "B13_B13") (pintype "passive"))
    )
    (net (code "112") (name "unconnected-(X3-PadB14)") (class "Default")
      (node (ref "X3") (pin "B14") (pinfunction "B14_B14") (pintype "passive"))
    )
    (net (code "113") (name "unconnected-(X3-PadB15)") (class "Default")
      (node (ref "X3") (pin "B15") (pinfunction "B15_B15") (pintype "passive"))
    )
    (net (code "114") (name "unconnected-(X3-PadB16)") (class "Default")
      (node (ref "X3") (pin "B16") (pinfunction "B16_B16") (pintype "passive"))
    )
    (net (code "115") (name "unconnected-(X3-PadB17)") (class "Default")
      (node (ref "X3") (pin "B17") (pinfunction "B17_B17") (pintype "passive"))
    )
    (net (code "116") (name "unconnected-(X3-PadB19)") (class "Default")
      (node (ref "X3") (pin "B19") (pinfunction "B19_B19") (pintype "passive"))
    )
    (net (code "117") (name "unconnected-(X3-PadB20)") (class "Default")
      (node (ref "X3") (pin "B20") (pinfunction "B20_B20") (pintype "passive"))
    )
    (net (code "118") (name "unconnected-(X3-PadB21)") (class "Default")
      (node (ref "X3") (pin "B21") (pinfunction "B21_B21") (pintype "passive"))
    )
    (net (code "119") (name "unconnected-(X3-PadB22)") (class "Default")
      (node (ref "X3") (pin "B22") (pinfunction "B22_B22") (pintype "passive"))
    )
    (net (code "120") (name "unconnected-(X3-PadB23)") (class "Default")
      (node (ref "X3") (pin "B23") (pinfunction "B23_B23") (pintype "passive"))
    )
    (net (code "121") (name "unconnected-(X3-PadB24)") (class "Default")
      (node (ref "X3") (pin "B24") (pinfunction "B24_B24") (pintype "passive"))
    )
    (net (code "122") (name "unconnected-(X3-PadB26)") (class "Default")
      (node (ref "X3") (pin "B26") (pinfunction "B26_B26") (pintype "passive"))
    )
    (net (code "123") (name "unconnected-(X3-PadB27)") (class "Default")
      (node (ref "X3") (pin "B27") (pinfunction "B27_B27") (pintype "passive"))
    )
    (net (code "124") (name "unconnected-(X3-PadB28)") (class "Default")
      (node (ref "X3") (pin "B28") (pinfunction "B28_B28") (pintype "passive"))
    )
    (net (code "125") (name "unconnected-(X3-PadB29)") (class "Default")
      (node (ref "X3") (pin "B29") (pinfunction "B29_B29") (pintype "passive"))
    )
    (net (code "126") (name "unconnected-(X3-PadB30)") (class "Default")
      (node (ref "X3") (pin "B30") (pinfunction "B30_B30") (pintype "passive"))
    )
    (net (code "127") (name "unconnected-(X3-PadB31)") (class "Default")
      (node (ref "X3") (pin "B31") (pinfunction "B31_B31") (pintype "passive"))
    )
    (net (code "128") (name "unconnected-(X4-Pad97)") (class "Default")
      (node (ref "X4") (pin "97") (pinfunction "97_97") (pintype "passive"))
    )
    (net (code "129") (name "unconnected-(X4-Pad98)") (class "Default")
      (node (ref "X4") (pin "98") (pinfunction "98_98") (pintype "passive"))
    )
    (net (code "130") (name "unconnected-(X4-PadA31)") (class "Default")
      (node (ref "X4") (pin "A31") (pinfunction "A31_A31") (pintype "passive"))
    )
    (net (code "131") (name "unconnected-(X4-PadB5)") (class "Default")
      (node (ref "X4") (pin "B5") (pinfunction "B5_B5") (pintype "passive"))
    )
    (net (code "132") (name "unconnected-(X4-PadB6)") (class "Default")
      (node (ref "X4") (pin "B6") (pinfunction "B6_B6") (pintype "passive"))
    )
    (net (code "133") (name "unconnected-(X4-PadB7)") (class "Default")
      (node (ref "X4") (pin "B7") (pinfunction "B7_B7") (pintype "passive"))
    )
    (net (code "134") (name "unconnected-(X4-PadB8)") (class "Default")
      (node (ref "X4") (pin "B8") (pinfunction "B8_B8") (pintype "passive"))
    )
    (net (code "135") (name "unconnected-(X4-PadB9)") (class "Default")
      (node (ref "X4") (pin "B9") (pinfunction "B9_B9") (pintype "passive"))
    )
    (net (code "136") (name "unconnected-(X4-PadB10)") (class "Default")
      (node (ref "X4") (pin "B10") (pinfunction "B10_B10") (pintype "passive"))
    )
    (net (code "137") (name "unconnected-(X4-PadB12)") (class "Default")
      (node (ref "X4") (pin "B12") (pinfunction "B12_B12") (pintype "passive"))
    )
    (net (code "138") (name "unconnected-(X4-PadB13)") (class "Default")
      (node (ref "X4") (pin "B13") (pinfunction "B13_B13") (pintype "passive"))
    )
    (net (code "139") (name "unconnected-(X4-PadB14)") (class "Default")
      (node (ref "X4") (pin "B14") (pinfunction "B14_B14") (pintype "passive"))
    )
    (net (code "140") (name "unconnected-(X4-PadB15)") (class "Default")
      (node (ref "X4") (pin "B15") (pinfunction "B15_B15") (pintype "passive"))
    )
    (net (code "141") (name "unconnected-(X4-PadB16)") (class "Default")
      (node (ref "X4") (pin "B16") (pinfunction "B16_B16") (pintype "passive"))
    )
    (net (code "142") (name "unconnected-(X4-PadB17)") (class "Default")
      (node (ref "X4") (pin "B17") (pinfunction "B17_B17") (pintype "passive"))
    )
    (net (code "143") (name "unconnected-(X4-PadB19)") (class "Default")
      (node (ref "X4") (pin "B19") (pinfunction "B19_B19") (pintype "passive"))
    )
    (net (code "144") (name "unconnected-(X4-PadB20)") (class "Default")
      (node (ref "X4") (pin "B20") (pinfunction "B20_B20") (pintype "passive"))
    )
    (net (code "145") (name "unconnected-(X4-PadB21)") (class "Default")
      (node (ref "X4") (pin "B21") (pinfunction "B21_B21") (pintype "passive"))
    )
    (net (code "146") (name "unconnected-(X4-PadB22)") (class "Default")
      (node (ref "X4") (pin "B22") (pinfunction "B22_B22") (pintype "passive"))
    )
    (net (code "147") (name "unconnected-(X4-PadB23)") (class "Default")
      (node (ref "X4") (pin "B23") (pinfunction "B23_B23") (pintype "passive"))
    )
    (net (code "148") (name "unconnected-(X4-PadB24)") (class "Default")
      (node (ref "X4") (pin "B24") (pinfunction "B24_B24") (pintype "passive"))
    )
    (net (code "149") (name "unconnected-(X4-PadB26)") (class "Default")
      (node (ref "X4") (pin "B26") (pinfunction "B26_B26") (pintype "passive"))
    )
    (net (code "150") (name "unconnected-(X4-PadB27)") (class "Default")
      (node (ref "X4") (pin "B27") (pinfunction "B27_B27") (pintype "passive"))
    )
    (net (code "151") (name "unconnected-(X4-PadB28)") (class "Default")
      (node (ref "X4") (pin "B28") (pinfunction "B28_B28") (pintype "passive"))
    )
    (net (code "152") (name "unconnected-(X4-PadB29)") (class "Default")
      (node (ref "X4") (pin "B29") (pinfunction "B29_B29") (pintype "passive"))
    )
    (net (code "153") (name "unconnected-(X4-PadB30)") (class "Default")
      (node (ref "X4") (pin "B30") (pinfunction "B30_B30") (pintype "passive"))
    )
    (net (code "154") (name "unconnected-(X4-PadB31)") (class "Default")
      (node (ref "X4") (pin "B31") (pinfunction "B31_B31") (pintype "passive"))
    )
    (net (code "155") (name "unconnected-(X5-Pad97)") (class "Default")
      (node (ref "X5") (pin "97") (pinfunction "97_97") (pintype "passive"))
    )
    (net (code "156") (name "unconnected-(X5-Pad98)") (class "Default")
      (node (ref "X5") (pin "98") (pinfunction "98_98") (pintype "passive"))
    )
    (net (code "157") (name "unconnected-(X5-PadA31)") (class "Default")
      (node (ref "X5") (pin "A31") (pinfunction "A31_A31") (pintype "passive"))
    )
    (net (code "158") (name "unconnected-(X5-PadB5)") (class "Default")
      (node (ref "X5") (pin "B5") (pinfunction "B5_B5") (pintype "passive"))
    )
    (net (code "159") (name "unconnected-(X5-PadB6)") (class "Default")
      (node (ref "X5") (pin "B6") (pinfunction "B6_B6") (pintype "passive"))
    )
    (net (code "160") (name "unconnected-(X5-PadB7)") (class "Default")
      (node (ref "X5") (pin "B7") (pinfunction "B7_B7") (pintype "passive"))
    )
    (net (code "161") (name "unconnected-(X5-PadB8)") (class "Default")
      (node (ref "X5") (pin "B8") (pinfunction "B8_B8") (pintype "passive"))
    )
    (net (code "162") (name "unconnected-(X5-PadB9)") (class "Default")
      (node (ref "X5") (pin "B9") (pinfunction "B9_B9") (pintype "passive"))
    )
    (net (code "163") (name "unconnected-(X5-PadB10)") (class "Default")
      (node (ref "X5") (pin "B10") (pinfunction "B10_B10") (pintype "passive"))
    )
    (net (code "164") (name "unconnected-(X5-PadB12)") (class "Default")
      (node (ref "X5") (pin "B12") (pinfunction "B12_B12") (pintype "passive"))
    )
    (net (code "165") (name "unconnected-(X5-PadB13)") (class "Default")
      (node (ref "X5") (pin "B13") (pinfunction "B13_B13") (pintype "passive"))
    )
    (net (code "166") (name "unconnected-(X5-PadB14)") (class "Default")
      (node (ref "X5") (pin "B14") (pinfunction "B14_B14") (pintype "passive"))
    )
    (net (code "167") (name "unconnected-(X5-PadB15)") (class "Default")
      (node (ref "X5") (pin "B15") (pinfunction "B15_B15") (pintype "passive"))
    )
    (net (code "168") (name "unconnected-(X5-PadB16)") (class "Default")
      (node (ref "X5") (pin "B16") (pinfunction "B16_B16") (pintype "passive"))
    )
    (net (code "169") (name "unconnected-(X5-PadB17)") (class "Default")
      (node (ref "X5") (pin "B17") (pinfunction "B17_B17") (pintype "passive"))
    )
    (net (code "170") (name "unconnected-(X5-PadB19)") (class "Default")
      (node (ref "X5") (pin "B19") (pinfunction "B19_B19") (pintype "passive"))
    )
    (net (code "171") (name "unconnected-(X5-PadB20)") (class "Default")
      (node (ref "X5") (pin "B20") (pinfunction "B20_B20") (pintype "passive"))
    )
    (net (code "172") (name "unconnected-(X5-PadB21)") (class "Default")
      (node (ref "X5") (pin "B21") (pinfunction "B21_B21") (pintype "passive"))
    )
    (net (code "173") (name "unconnected-(X5-PadB22)") (class "Default")
      (node (ref "X5") (pin "B22") (pinfunction "B22_B22") (pintype "passive"))
    )
    (net (code "174") (name "unconnected-(X5-PadB23)") (class "Default")
      (node (ref "X5") (pin "B23") (pinfunction "B23_B23") (pintype "passive"))
    )
    (net (code "175") (name "unconnected-(X5-PadB24)") (class "Default")
      (node (ref "X5") (pin "B24") (pinfunction "B24_B24") (pintype "passive"))
    )
    (net (code "176") (name "unconnected-(X5-PadB26)") (class "Default")
      (node (ref "X5") (pin "B26") (pinfunction "B26_B26") (pintype "passive"))
    )
    (net (code "177") (name "unconnected-(X5-PadB27)") (class "Default")
      (node (ref "X5") (pin "B27") (pinfunction "B27_B27") (pintype "passive"))
    )
    (net (code "178") (name "unconnected-(X5-PadB28)") (class "Default")
      (node (ref "X5") (pin "B28") (pinfunction "B28_B28") (pintype "passive"))
    )
    (net (code "179") (name "unconnected-(X5-PadB29)") (class "Default")
      (node (ref "X5") (pin "B29") (pinfunction "B29_B29") (pintype "passive"))
    )
    (net (code "180") (name "unconnected-(X5-PadB30)") (class "Default")
      (node (ref "X5") (pin "B30") (pinfunction "B30_B30") (pintype "passive"))
    )
    (net (code "181") (name "unconnected-(X5-PadB31)") (class "Default")
      (node (ref "X5") (pin "B31") (pinfunction "B31_B31") (pintype "passive"))
    )
    (net (code "182") (name "unconnected-(X6-Pad97)") (class "Default")
      (node (ref "X6") (pin "97") (pinfunction "97_97") (pintype "passive"))
    )
    (net (code "183") (name "unconnected-(X6-Pad98)") (class "Default")
      (node (ref "X6") (pin "98") (pinfunction "98_98") (pintype "passive"))
    )
    (net (code "184") (name "unconnected-(X6-PadA31)") (class "Default")
      (node (ref "X6") (pin "A31") (pinfunction "A31_A31") (pintype "passive"))
    )
    (net (code "185") (name "unconnected-(X6-PadB5)") (class "Default")
      (node (ref "X6") (pin "B5") (pinfunction "B5_B5") (pintype "passive"))
    )
    (net (code "186") (name "unconnected-(X6-PadB6)") (class "Default")
      (node (ref "X6") (pin "B6") (pinfunction "B6_B6") (pintype "passive"))
    )
    (net (code "187") (name "unconnected-(X6-PadB7)") (class "Default")
      (node (ref "X6") (pin "B7") (pinfunction "B7_B7") (pintype "passive"))
    )
    (net (code "188") (name "unconnected-(X6-PadB8)") (class "Default")
      (node (ref "X6") (pin "B8") (pinfunction "B8_B8") (pintype "passive"))
    )
    (net (code "189") (name "unconnected-(X6-PadB9)") (class "Default")
      (node (ref "X6") (pin "B9") (pinfunction "B9_B9") (pintype "passive"))
    )
    (net (code "190") (name "unconnected-(X6-PadB10)") (class "Default")
      (node (ref "X6") (pin "B10") (pinfunction "B10_B10") (pintype "passive"))
    )
    (net (code "191") (name "unconnected-(X6-PadB12)") (class "Default")
      (node (ref "X6") (pin "B12") (pinfunction "B12_B12") (pintype "passive"))
    )
    (net (code "192") (name "unconnected-(X6-PadB13)") (class "Default")
      (node (ref "X6") (pin "B13") (pinfunction "B13_B13") (pintype "passive"))
    )
    (net (code "193") (name "unconnected-(X6-PadB14)") (class "Default")
      (node (ref "X6") (pin "B14") (pinfunction "B14_B14") (pintype "passive"))
    )
    (net (code "194") (name "unconnected-(X6-PadB15)") (class "Default")
      (node (ref "X6") (pin "B15") (pinfunction "B15_B15") (pintype "passive"))
    )
    (net (code "195") (name "unconnected-(X6-PadB16)") (class "Default")
      (node (ref "X6") (pin "B16") (pinfunction "B16_B16") (pintype "passive"))
    )
    (net (code "196") (name "unconnected-(X6-PadB17)") (class "Default")
      (node (ref "X6") (pin "B17") (pinfunction "B17_B17") (pintype "passive"))
    )
    (net (code "197") (name "unconnected-(X6-PadB19)") (class "Default")
      (node (ref "X6") (pin "B19") (pinfunction "B19_B19") (pintype "passive"))
    )
    (net (code "198") (name "unconnected-(X6-PadB20)") (class "Default")
      (node (ref "X6") (pin "B20") (pinfunction "B20_B20") (pintype "passive"))
    )
    (net (code "199") (name "unconnected-(X6-PadB21)") (class "Default")
      (node (ref "X6") (pin "B21") (pinfunction "B21_B21") (pintype "passive"))
    )
    (net (code "200") (name "unconnected-(X6-PadB22)") (class "Default")
      (node (ref "X6") (pin "B22") (pinfunction "B22_B22") (pintype "passive"))
    )
    (net (code "201") (name "unconnected-(X6-PadB23)") (class "Default")
      (node (ref "X6") (pin "B23") (pinfunction "B23_B23") (pintype "passive"))
    )
    (net (code "202") (name "unconnected-(X6-PadB24)") (class "Default")
      (node (ref "X6") (pin "B24") (pinfunction "B24_B24") (pintype "passive"))
    )
    (net (code "203") (name "unconnected-(X6-PadB26)") (class "Default")
      (node (ref "X6") (pin "B26") (pinfunction "B26_B26") (pintype "passive"))
    )
    (net (code "204") (name "unconnected-(X6-PadB27)") (class "Default")
      (node (ref "X6") (pin "B27") (pinfunction "B27_B27") (pintype "passive"))
    )
    (net (code "205") (name "unconnected-(X6-PadB28)") (class "Default")
      (node (ref "X6") (pin "B28") (pinfunction "B28_B28") (pintype "passive"))
    )
    (net (code "206") (name "unconnected-(X6-PadB29)") (class "Default")
      (node (ref "X6") (pin "B29") (pinfunction "B29_B29") (pintype "passive"))
    )
    (net (code "207") (name "unconnected-(X6-PadB30)") (class "Default")
      (node (ref "X6") (pin "B30") (pinfunction "B30_B30") (pintype "passive"))
    )
    (net (code "208") (name "unconnected-(X6-PadB31)") (class "Default")
      (node (ref "X6") (pin "B31") (pinfunction "B31_B31") (pintype "passive"))
    )
    (net (code "209") (name "unconnected-(X7-Pad97)") (class "Default")
      (node (ref "X7") (pin "97") (pinfunction "97_97") (pintype "passive"))
    )
    (net (code "210") (name "unconnected-(X7-Pad98)") (class "Default")
      (node (ref "X7") (pin "98") (pinfunction "98_98") (pintype "passive"))
    )
    (net (code "211") (name "unconnected-(X7-PadB5)") (class "Default")
      (node (ref "X7") (pin "B5") (pinfunction "B5_B5") (pintype "passive"))
    )
    (net (code "212") (name "unconnected-(X7-PadB6)") (class "Default")
      (node (ref "X7") (pin "B6") (pinfunction "B6_B6") (pintype "passive"))
    )
    (net (code "213") (name "unconnected-(X7-PadB7)") (class "Default")
      (node (ref "X7") (pin "B7") (pinfunction "B7_B7") (pintype "passive"))
    )
    (net (code "214") (name "unconnected-(X7-PadB8)") (class "Default")
      (node (ref "X7") (pin "B8") (pinfunction "B8_B8") (pintype "passive"))
    )
    (net (code "215") (name "unconnected-(X7-PadB9)") (class "Default")
      (node (ref "X7") (pin "B9") (pinfunction "B9_B9") (pintype "passive"))
    )
    (net (code "216") (name "unconnected-(X7-PadB10)") (class "Default")
      (node (ref "X7") (pin "B10") (pinfunction "B10_B10") (pintype "passive"))
    )
    (net (code "217") (name "unconnected-(X7-PadB12)") (class "Default")
      (node (ref "X7") (pin "B12") (pinfunction "B12_B12") (pintype "passive"))
    )
    (net (code "218") (name "unconnected-(X7-PadB13)") (class "Default")
      (node (ref "X7") (pin "B13") (pinfunction "B13_B13") (pintype "passive"))
    )
    (net (code "219") (name "unconnected-(X7-PadB14)") (class "Default")
      (node (ref "X7") (pin "B14") (pinfunction "B14_B14") (pintype "passive"))
    )
    (net (code "220") (name "unconnected-(X7-PadB15)") (class "Default")
      (node (ref "X7") (pin "B15") (pinfunction "B15_B15") (pintype "passive"))
    )
    (net (code "221") (name "unconnected-(X7-PadB16)") (class "Default")
      (node (ref "X7") (pin "B16") (pinfunction "B16_B16") (pintype "passive"))
    )
    (net (code "222") (name "unconnected-(X7-PadB17)") (class "Default")
      (node (ref "X7") (pin "B17") (pinfunction "B17_B17") (pintype "passive"))
    )
    (net (code "223") (name "unconnected-(X7-PadB19)") (class "Default")
      (node (ref "X7") (pin "B19") (pinfunction "B19_B19") (pintype "passive"))
    )
    (net (code "224") (name "unconnected-(X7-PadB20)") (class "Default")
      (node (ref "X7") (pin "B20") (pinfunction "B20_B20") (pintype "passive"))
    )
    (net (code "225") (name "unconnected-(X7-PadB21)") (class "Default")
      (node (ref "X7") (pin "B21") (pinfunction "B21_B21") (pintype "passive"))
    )
    (net (code "226") (name "unconnected-(X7-PadB22)") (class "Default")
      (node (ref "X7") (pin "B22") (pinfunction "B22_B22") (pintype "passive"))
    )
    (net (code "227") (name "unconnected-(X7-PadB23)") (class "Default")
      (node (ref "X7") (pin "B23") (pinfunction "B23_B23") (pintype "passive"))
    )
    (net (code "228") (name "unconnected-(X7-PadB24)") (class "Default")
      (node (ref "X7") (pin "B24") (pinfunction "B24_B24") (pintype "passive"))
    )
    (net (code "229") (name "unconnected-(X7-PadB26)") (class "Default")
      (node (ref "X7") (pin "B26") (pinfunction "B26_B26") (pintype "passive"))
    )
    (net (code "230") (name "unconnected-(X7-PadB27)") (class "Default")
      (node (ref "X7") (pin "B27") (pinfunction "B27_B27") (pintype "passive"))
    )
    (net (code "231") (name "unconnected-(X7-PadB28)") (class "Default")
      (node (ref "X7") (pin "B28") (pinfunction "B28_B28") (pintype "passive"))
    )
    (net (code "232") (name "unconnected-(X7-PadB29)") (class "Default")
      (node (ref "X7") (pin "B29") (pinfunction "B29_B29") (pintype "passive"))
    )
    (net (code "233") (name "unconnected-(X8-Pad97)") (class "Default")
      (node (ref "X8") (pin "97") (pinfunction "97_97") (pintype "passive"))
    )
    (net (code "234") (name "unconnected-(X8-Pad98)") (class "Default")
      (node (ref "X8") (pin "98") (pinfunction "98_98") (pintype "passive"))
    )
    (net (code "235") (name "unconnected-(X8-PadB5)") (class "Default")
      (node (ref "X8") (pin "B5") (pinfunction "B5_B5") (pintype "passive"))
    )
    (net (code "236") (name "unconnected-(X8-PadB6)") (class "Default")
      (node (ref "X8") (pin "B6") (pinfunction "B6_B6") (pintype "passive"))
    )
    (net (code "237") (name "unconnected-(X8-PadB7)") (class "Default")
      (node (ref "X8") (pin "B7") (pinfunction "B7_B7") (pintype "passive"))
    )
    (net (code "238") (name "unconnected-(X8-PadB8)") (class "Default")
      (node (ref "X8") (pin "B8") (pinfunction "B8_B8") (pintype "passive"))
    )
    (net (code "239") (name "unconnected-(X8-PadB9)") (class "Default")
      (node (ref "X8") (pin "B9") (pinfunction "B9_B9") (pintype "passive"))
    )
    (net (code "240") (name "unconnected-(X8-PadB10)") (class "Default")
      (node (ref "X8") (pin "B10") (pinfunction "B10_B10") (pintype "passive"))
    )
    (net (code "241") (name "unconnected-(X8-PadB12)") (class "Default")
      (node (ref "X8") (pin "B12") (pinfunction "B12_B12") (pintype "passive"))
    )
    (net (code "242") (name "unconnected-(X8-PadB13)") (class "Default")
      (node (ref "X8") (pin "B13") (pinfunction "B13_B13") (pintype "passive"))
    )
    (net (code "243") (name "unconnected-(X8-PadB14)") (class "Default")
      (node (ref "X8") (pin "B14") (pinfunction "B14_B14") (pintype "passive"))
    )
    (net (code "244") (name "unconnected-(X8-PadB15)") (class "Default")
      (node (ref "X8") (pin "B15") (pinfunction "B15_B15") (pintype "passive"))
    )
    (net (code "245") (name "unconnected-(X8-PadB16)") (class "Default")
      (node (ref "X8") (pin "B16") (pinfunction "B16_B16") (pintype "passive"))
    )
    (net (code "246") (name "unconnected-(X8-PadB17)") (class "Default")
      (node (ref "X8") (pin "B17") (pinfunction "B17_B17") (pintype "passive"))
    )
    (net (code "247") (name "unconnected-(X8-PadB19)") (class "Default")
      (node (ref "X8") (pin "B19") (pinfunction "B19_B19") (pintype "passive"))
    )
    (net (code "248") (name "unconnected-(X8-PadB20)") (class "Default")
      (node (ref "X8") (pin "B20") (pinfunction "B20_B20") (pintype "passive"))
    )
    (net (code "249") (name "unconnected-(X8-PadB21)") (class "Default")
      (node (ref "X8") (pin "B21") (pinfunction "B21_B21") (pintype "passive"))
    )
    (net (code "250") (name "unconnected-(X8-PadB22)") (class "Default")
      (node (ref "X8") (pin "B22") (pinfunction "B22_B22") (pintype "passive"))
    )
    (net (code "251") (name "unconnected-(X8-PadB23)") (class "Default")
      (node (ref "X8") (pin "B23") (pinfunction "B23_B23") (pintype "passive"))
    )
    (net (code "252") (name "unconnected-(X8-PadB24)") (class "Default")
      (node (ref "X8") (pin "B24") (pinfunction "B24_B24") (pintype "passive"))
    )
    (net (code "253") (name "unconnected-(X8-PadB26)") (class "Default")
      (node (ref "X8") (pin "B26") (pinfunction "B26_B26") (pintype "passive"))
    )
    (net (code "254") (name "unconnected-(X8-PadB27)") (class "Default")
      (node (ref "X8") (pin "B27") (pinfunction "B27_B27") (pintype "passive"))
    )
    (net (code "255") (name "unconnected-(X8-PadB28)") (class "Default")
      (node (ref "X8") (pin "B28") (pinfunction "B28_B28") (pintype "passive"))
    )
    (net (code "256") (name "unconnected-(X8-PadB29)") (class "Default")
      (node (ref "X8") (pin "B29") (pinfunction "B29_B29") (pintype "passive"))
    )
    (net (code "257") (name "unconnected-(X9-Pad97)") (class "Default")
      (node (ref "X9") (pin "97") (pinfunction "97_97") (pintype "passive"))
    )
    (net (code "258") (name "unconnected-(X9-Pad98)") (class "Default")
      (node (ref "X9") (pin "98") (pinfunction "98_98") (pintype "passive"))
    )
    (net (code "259") (name "unconnected-(X9-PadA31)") (class "Default")
      (node (ref "X9") (pin "A31") (pinfunction "A31_A31") (pintype "passive"))
    )
    (net (code "260") (name "unconnected-(X9-PadB5)") (class "Default")
      (node (ref "X9") (pin "B5") (pinfunction "B5_B5") (pintype "passive"))
    )
    (net (code "261") (name "unconnected-(X9-PadB6)") (class "Default")
      (node (ref "X9") (pin "B6") (pinfunction "B6_B6") (pintype "passive"))
    )
    (net (code "262") (name "unconnected-(X9-PadB7)") (class "Default")
      (node (ref "X9") (pin "B7") (pinfunction "B7_B7") (pintype "passive"))
    )
    (net (code "263") (name "unconnected-(X9-PadB8)") (class "Default")
      (node (ref "X9") (pin "B8") (pinfunction "B8_B8") (pintype "passive"))
    )
    (net (code "264") (name "unconnected-(X9-PadB9)") (class "Default")
      (node (ref "X9") (pin "B9") (pinfunction "B9_B9") (pintype "passive"))
    )
    (net (code "265") (name "unconnected-(X9-PadB10)") (class "Default")
      (node (ref "X9") (pin "B10") (pinfunction "B10_B10") (pintype "passive"))
    )
    (net (code "266") (name "unconnected-(X9-PadB12)") (class "Default")
      (node (ref "X9") (pin "B12") (pinfunction "B12_B12") (pintype "passive"))
    )
    (net (code "267") (name "unconnected-(X9-PadB13)") (class "Default")
      (node (ref "X9") (pin "B13") (pinfunction "B13_B13") (pintype "passive"))
    )
    (net (code "268") (name "unconnected-(X9-PadB14)") (class "Default")
      (node (ref "X9") (pin "B14") (pinfunction "B14_B14") (pintype "passive"))
    )
    (net (code "269") (name "unconnected-(X9-PadB15)") (class "Default")
      (node (ref "X9") (pin "B15") (pinfunction "B15_B15") (pintype "passive"))
    )
    (net (code "270") (name "unconnected-(X9-PadB16)") (class "Default")
      (node (ref "X9") (pin "B16") (pinfunction "B16_B16") (pintype "passive"))
    )
    (net (code "271") (name "unconnected-(X9-PadB17)") (class "Default")
      (node (ref "X9") (pin "B17") (pinfunction "B17_B17") (pintype "passive"))
    )
    (net (code "272") (name "unconnected-(X9-PadB19)") (class "Default")
      (node (ref "X9") (pin "B19") (pinfunction "B19_B19") (pintype "passive"))
    )
    (net (code "273") (name "unconnected-(X9-PadB20)") (class "Default")
      (node (ref "X9") (pin "B20") (pinfunction "B20_B20") (pintype "passive"))
    )
    (net (code "274") (name "unconnected-(X9-PadB21)") (class "Default")
      (node (ref "X9") (pin "B21") (pinfunction "B21_B21") (pintype "passive"))
    )
    (net (code "275") (name "unconnected-(X9-PadB22)") (class "Default")
      (node (ref "X9") (pin "B22") (pinfunction "B22_B22") (pintype "passive"))
    )
    (net (code "276") (name "unconnected-(X9-PadB23)") (class "Default")
      (node (ref "X9") (pin "B23") (pinfunction "B23_B23") (pintype "passive"))
    )
    (net (code "277") (name "unconnected-(X9-PadB24)") (class "Default")
      (node (ref "X9") (pin "B24") (pinfunction "B24_B24") (pintype "passive"))
    )
    (net (code "278") (name "unconnected-(X9-PadB26)") (class "Default")
      (node (ref "X9") (pin "B26") (pinfunction "B26_B26") (pintype "passive"))
    )
    (net (code "279") (name "unconnected-(X9-PadB27)") (class "Default")
      (node (ref "X9") (pin "B27") (pinfunction "B27_B27") (pintype "passive"))
    )
    (net (code "280") (name "unconnected-(X9-PadB28)") (class "Default")
      (node (ref "X9") (pin "B28") (pinfunction "B28_B28") (pintype "passive"))
    )
    (net (code "281") (name "unconnected-(X9-PadB29)") (class "Default")
      (node (ref "X9") (pin "B29") (pinfunction "B29_B29") (pintype "passive"))
    )
    (net (code "282") (name "unconnected-(X9-PadB30)") (class "Default")
      (node (ref "X9") (pin "B30") (pinfunction "B30_B30") (pintype "passive"))
    )
    (net (code "283") (name "unconnected-(X9-PadB31)") (class "Default")
      (node (ref "X9") (pin "B31") (pinfunction "B31_B31") (pintype "passive"))
    )
    (net (code "284") (name "unconnected-(X10-Pad97)") (class "Default")
      (node (ref "X10") (pin "97") (pinfunction "97_97") (pintype "passive"))
    )
    (net (code "285") (name "unconnected-(X10-Pad98)") (class "Default")
      (node (ref "X10") (pin "98") (pinfunction "98_98") (pintype "passive"))
    )
    (net (code "286") (name "unconnected-(X10-PadA31)") (class "Default")
      (node (ref "X10") (pin "A31") (pinfunction "A31_A31") (pintype "passive"))
    )
    (net (code "287") (name "unconnected-(X10-PadB5)") (class "Default")
      (node (ref "X10") (pin "B5") (pinfunction "B5_B5") (pintype "passive"))
    )
    (net (code "288") (name "unconnected-(X10-PadB6)") (class "Default")
      (node (ref "X10") (pin "B6") (pinfunction "B6_B6") (pintype "passive"))
    )
    (net (code "289") (name "unconnected-(X10-PadB7)") (class "Default")
      (node (ref "X10") (pin "B7") (pinfunction "B7_B7") (pintype "passive"))
    )
    (net (code "290") (name "unconnected-(X10-PadB8)") (class "Default")
      (node (ref "X10") (pin "B8") (pinfunction "B8_B8") (pintype "passive"))
    )
    (net (code "291") (name "unconnected-(X10-PadB9)") (class "Default")
      (node (ref "X10") (pin "B9") (pinfunction "B9_B9") (pintype "passive"))
    )
    (net (code "292") (name "unconnected-(X10-PadB10)") (class "Default")
      (node (ref "X10") (pin "B10") (pinfunction "B10_B10") (pintype "passive"))
    )
    (net (code "293") (name "unconnected-(X10-PadB12)") (class "Default")
      (node (ref "X10") (pin "B12") (pinfunction "B12_B12") (pintype "passive"))
    )
    (net (code "294") (name "unconnected-(X10-PadB13)") (class "Default")
      (node (ref "X10") (pin "B13") (pinfunction "B13_B13") (pintype "passive"))
    )
    (net (code "295") (name "unconnected-(X10-PadB14)") (class "Default")
      (node (ref "X10") (pin "B14") (pinfunction "B14_B14") (pintype "passive"))
    )
    (net (code "296") (name "unconnected-(X10-PadB15)") (class "Default")
      (node (ref "X10") (pin "B15") (pinfunction "B15_B15") (pintype "passive"))
    )
    (net (code "297") (name "unconnected-(X10-PadB16)") (class "Default")
      (node (ref "X10") (pin "B16") (pinfunction "B16_B16") (pintype "passive"))
    )
    (net (code "298") (name "unconnected-(X10-PadB17)") (class "Default")
      (node (ref "X10") (pin "B17") (pinfunction "B17_B17") (pintype "passive"))
    )
    (net (code "299") (name "unconnected-(X10-PadB19)") (class "Default")
      (node (ref "X10") (pin "B19") (pinfunction "B19_B19") (pintype "passive"))
    )
    (net (code "300") (name "unconnected-(X10-PadB20)") (class "Default")
      (node (ref "X10") (pin "B20") (pinfunction "B20_B20") (pintype "passive"))
    )
    (net (code "301") (name "unconnected-(X10-PadB21)") (class "Default")
      (node (ref "X10") (pin "B21") (pinfunction "B21_B21") (pintype "passive"))
    )
    (net (code "302") (name "unconnected-(X10-PadB22)") (class "Default")
      (node (ref "X10") (pin "B22") (pinfunction "B22_B22") (pintype "passive"))
    )
    (net (code "303") (name "unconnected-(X10-PadB23)") (class "Default")
      (node (ref "X10") (pin "B23") (pinfunction "B23_B23") (pintype "passive"))
    )
    (net (code "304") (name "unconnected-(X10-PadB24)") (class "Default")
      (node (ref "X10") (pin "B24") (pinfunction "B24_B24") (pintype "passive"))
    )
    (net (code "305") (name "unconnected-(X10-PadB26)") (class "Default")
      (node (ref "X10") (pin "B26") (pinfunction "B26_B26") (pintype "passive"))
    )
    (net (code "306") (name "unconnected-(X10-PadB27)") (class "Default")
      (node (ref "X10") (pin "B27") (pinfunction "B27_B27") (pintype "passive"))
    )
    (net (code "307") (name "unconnected-(X10-PadB28)") (class "Default")
      (node (ref "X10") (pin "B28") (pinfunction "B28_B28") (pintype "passive"))
    )
    (net (code "308") (name "unconnected-(X10-PadB29)") (class "Default")
      (node (ref "X10") (pin "B29") (pinfunction "B29_B29") (pintype "passive"))
    )
    (net (code "309") (name "unconnected-(X10-PadB30)") (class "Default")
      (node (ref "X10") (pin "B30") (pinfunction "B30_B30") (pintype "passive"))
    )
    (net (code "310") (name "unconnected-(X10-PadB31)") (class "Default")
      (node (ref "X10") (pin "B31") (pinfunction "B31_B31") (pintype "passive"))
    )
    (net (code "311") (name "unconnected-(X11-Pad97)") (class "Default")
      (node (ref "X11") (pin "97") (pinfunction "97_97") (pintype "passive"))
    )
    (net (code "312") (name "unconnected-(X11-Pad98)") (class "Default")
      (node (ref "X11") (pin "98") (pinfunction "98_98") (pintype "passive"))
    )
    (net (code "313") (name "unconnected-(X11-PadA31)") (class "Default")
      (node (ref "X11") (pin "A31") (pinfunction "A31_A31") (pintype "passive"))
    )
    (net (code "314") (name "unconnected-(X11-PadB5)") (class "Default")
      (node (ref "X11") (pin "B5") (pinfunction "B5_B5") (pintype "passive"))
    )
    (net (code "315") (name "unconnected-(X11-PadB6)") (class "Default")
      (node (ref "X11") (pin "B6") (pinfunction "B6_B6") (pintype "passive"))
    )
    (net (code "316") (name "unconnected-(X11-PadB7)") (class "Default")
      (node (ref "X11") (pin "B7") (pinfunction "B7_B7") (pintype "passive"))
    )
    (net (code "317") (name "unconnected-(X11-PadB8)") (class "Default")
      (node (ref "X11") (pin "B8") (pinfunction "B8_B8") (pintype "passive"))
    )
    (net (code "318") (name "unconnected-(X11-PadB9)") (class "Default")
      (node (ref "X11") (pin "B9") (pinfunction "B9_B9") (pintype "passive"))
    )
    (net (code "319") (name "unconnected-(X11-PadB10)") (class "Default")
      (node (ref "X11") (pin "B10") (pinfunction "B10_B10") (pintype "passive"))
    )
    (net (code "320") (name "unconnected-(X11-PadB12)") (class "Default")
      (node (ref "X11") (pin "B12") (pinfunction "B12_B12") (pintype "passive"))
    )
    (net (code "321") (name "unconnected-(X11-PadB13)") (class "Default")
      (node (ref "X11") (pin "B13") (pinfunction "B13_B13") (pintype "passive"))
    )
    (net (code "322") (name "unconnected-(X11-PadB14)") (class "Default")
      (node (ref "X11") (pin "B14") (pinfunction "B14_B14") (pintype "passive"))
    )
    (net (code "323") (name "unconnected-(X11-PadB15)") (class "Default")
      (node (ref "X11") (pin "B15") (pinfunction "B15_B15") (pintype "passive"))
    )
    (net (code "324") (name "unconnected-(X11-PadB16)") (class "Default")
      (node (ref "X11") (pin "B16") (pinfunction "B16_B16") (pintype "passive"))
    )
    (net (code "325") (name "unconnected-(X11-PadB17)") (class "Default")
      (node (ref "X11") (pin "B17") (pinfunction "B17_B17") (pintype "passive"))
    )
    (net (code "326") (name "unconnected-(X11-PadB19)") (class "Default")
      (node (ref "X11") (pin "B19") (pinfunction "B19_B19") (pintype "passive"))
    )
    (net (code "327") (name "unconnected-(X11-PadB20)") (class "Default")
      (node (ref "X11") (pin "B20") (pinfunction "B20_B20") (pintype "passive"))
    )
    (net (code "328") (name "unconnected-(X11-PadB21)") (class "Default")
      (node (ref "X11") (pin "B21") (pinfunction "B21_B21") (pintype "passive"))
    )
    (net (code "329") (name "unconnected-(X11-PadB22)") (class "Default")
      (node (ref "X11") (pin "B22") (pinfunction "B22_B22") (pintype "passive"))
    )
    (net (code "330") (name "unconnected-(X11-PadB23)") (class "Default")
      (node (ref "X11") (pin "B23") (pinfunction "B23_B23") (pintype "passive"))
    )
    (net (code "331") (name "unconnected-(X11-PadB24)") (class "Default")
      (node (ref "X11") (pin "B24") (pinfunction "B24_B24") (pintype "passive"))
    )
    (net (code "332") (name "unconnected-(X11-PadB26)") (class "Default")
      (node (ref "X11") (pin "B26") (pinfunction "B26_B26") (pintype "passive"))
    )
    (net (code "333") (name "unconnected-(X11-PadB27)") (class "Default")
      (node (ref "X11") (pin "B27") (pinfunction "B27_B27") (pintype "passive"))
    )
    (net (code "334") (name "unconnected-(X11-PadB28)") (class "Default")
      (node (ref "X11") (pin "B28") (pinfunction "B28_B28") (pintype "passive"))
    )
    (net (code "335") (name "unconnected-(X11-PadB29)") (class "Default")
      (node (ref "X11") (pin "B29") (pinfunction "B29_B29") (pintype "passive"))
    )
    (net (code "336") (name "unconnected-(X11-PadB30)") (class "Default")
      (node (ref "X11") (pin "B30") (pinfunction "B30_B30") (pintype "passive"))
    )
    (net (code "337") (name "unconnected-(X11-PadB31)") (class "Default")
      (node (ref "X11") (pin "B31") (pinfunction "B31_B31") (pintype "passive"))
    )
    (net (code "338") (name "unconnected-(X12-Pad97)") (class "Default")
      (node (ref "X12") (pin "97") (pinfunction "97_97") (pintype "passive"))
    )
    (net (code "339") (name "unconnected-(X12-Pad98)") (class "Default")
      (node (ref "X12") (pin "98") (pinfunction "98_98") (pintype "passive"))
    )
    (net (code "340") (name "unconnected-(X12-PadA31)") (class "Default")
      (node (ref "X12") (pin "A31") (pinfunction "A31_A31") (pintype "passive"))
    )
    (net (code "341") (name "unconnected-(X12-PadB5)") (class "Default")
      (node (ref "X12") (pin "B5") (pinfunction "B5_B5") (pintype "passive"))
    )
    (net (code "342") (name "unconnected-(X12-PadB6)") (class "Default")
      (node (ref "X12") (pin "B6") (pinfunction "B6_B6") (pintype "passive"))
    )
    (net (code "343") (name "unconnected-(X12-PadB7)") (class "Default")
      (node (ref "X12") (pin "B7") (pinfunction "B7_B7") (pintype "passive"))
    )
    (net (code "344") (name "unconnected-(X12-PadB8)") (class "Default")
      (node (ref "X12") (pin "B8") (pinfunction "B8_B8") (pintype "passive"))
    )
    (net (code "345") (name "unconnected-(X12-PadB9)") (class "Default")
      (node (ref "X12") (pin "B9") (pinfunction "B9_B9") (pintype "passive"))
    )
    (net (code "346") (name "unconnected-(X12-PadB10)") (class "Default")
      (node (ref "X12") (pin "B10") (pinfunction "B10_B10") (pintype "passive"))
    )
    (net (code "347") (name "unconnected-(X12-PadB12)") (class "Default")
      (node (ref "X12") (pin "B12") (pinfunction "B12_B12") (pintype "passive"))
    )
    (net (code "348") (name "unconnected-(X12-PadB13)") (class "Default")
      (node (ref "X12") (pin "B13") (pinfunction "B13_B13") (pintype "passive"))
    )
    (net (code "349") (name "unconnected-(X12-PadB14)") (class "Default")
      (node (ref "X12") (pin "B14") (pinfunction "B14_B14") (pintype "passive"))
    )
    (net (code "350") (name "unconnected-(X12-PadB15)") (class "Default")
      (node (ref "X12") (pin "B15") (pinfunction "B15_B15") (pintype "passive"))
    )
    (net (code "351") (name "unconnected-(X12-PadB16)") (class "Default")
      (node (ref "X12") (pin "B16") (pinfunction "B16_B16") (pintype "passive"))
    )
    (net (code "352") (name "unconnected-(X12-PadB17)") (class "Default")
      (node (ref "X12") (pin "B17") (pinfunction "B17_B17") (pintype "passive"))
    )
    (net (code "353") (name "unconnected-(X12-PadB19)") (class "Default")
      (node (ref "X12") (pin "B19") (pinfunction "B19_B19") (pintype "passive"))
    )
    (net (code "354") (name "unconnected-(X12-PadB20)") (class "Default")
      (node (ref "X12") (pin "B20") (pinfunction "B20_B20") (pintype "passive"))
    )
    (net (code "355") (name "unconnected-(X12-PadB21)") (class "Default")
      (node (ref "X12") (pin "B21") (pinfunction "B21_B21") (pintype "passive"))
    )
    (net (code "356") (name "unconnected-(X12-PadB22)") (class "Default")
      (node (ref "X12") (pin "B22") (pinfunction "B22_B22") (pintype "passive"))
    )
    (net (code "357") (name "unconnected-(X12-PadB23)") (class "Default")
      (node (ref "X12") (pin "B23") (pinfunction "B23_B23") (pintype "passive"))
    )
    (net (code "358") (name "unconnected-(X12-PadB24)") (class "Default")
      (node (ref "X12") (pin "B24") (pinfunction "B24_B24") (pintype "passive"))
    )
    (net (code "359") (name "unconnected-(X12-PadB26)") (class "Default")
      (node (ref "X12") (pin "B26") (pinfunction "B26_B26") (pintype "passive"))
    )
    (net (code "360") (name "unconnected-(X12-PadB27)") (class "Default")
      (node (ref "X12") (pin "B27") (pinfunction "B27_B27") (pintype "passive"))
    )
    (net (code "361") (name "unconnected-(X12-PadB28)") (class "Default")
      (node (ref "X12") (pin "B28") (pinfunction "B28_B28") (pintype "passive"))
    )
    (net (code "362") (name "unconnected-(X12-PadB29)") (class "Default")
      (node (ref "X12") (pin "B29") (pinfunction "B29_B29") (pintype "passive"))
    )
    (net (code "363") (name "unconnected-(X12-PadB30)") (class "Default")
      (node (ref "X12") (pin "B30") (pinfunction "B30_B30") (pintype "passive"))
    )
    (net (code "364") (name "unconnected-(X12-PadB31)") (class "Default")
      (node (ref "X12") (pin "B31") (pinfunction "B31_B31") (pintype "passive"))
    )
  )
)
